# r.net
KiCad netlist of a schematic drawn in EAGLE
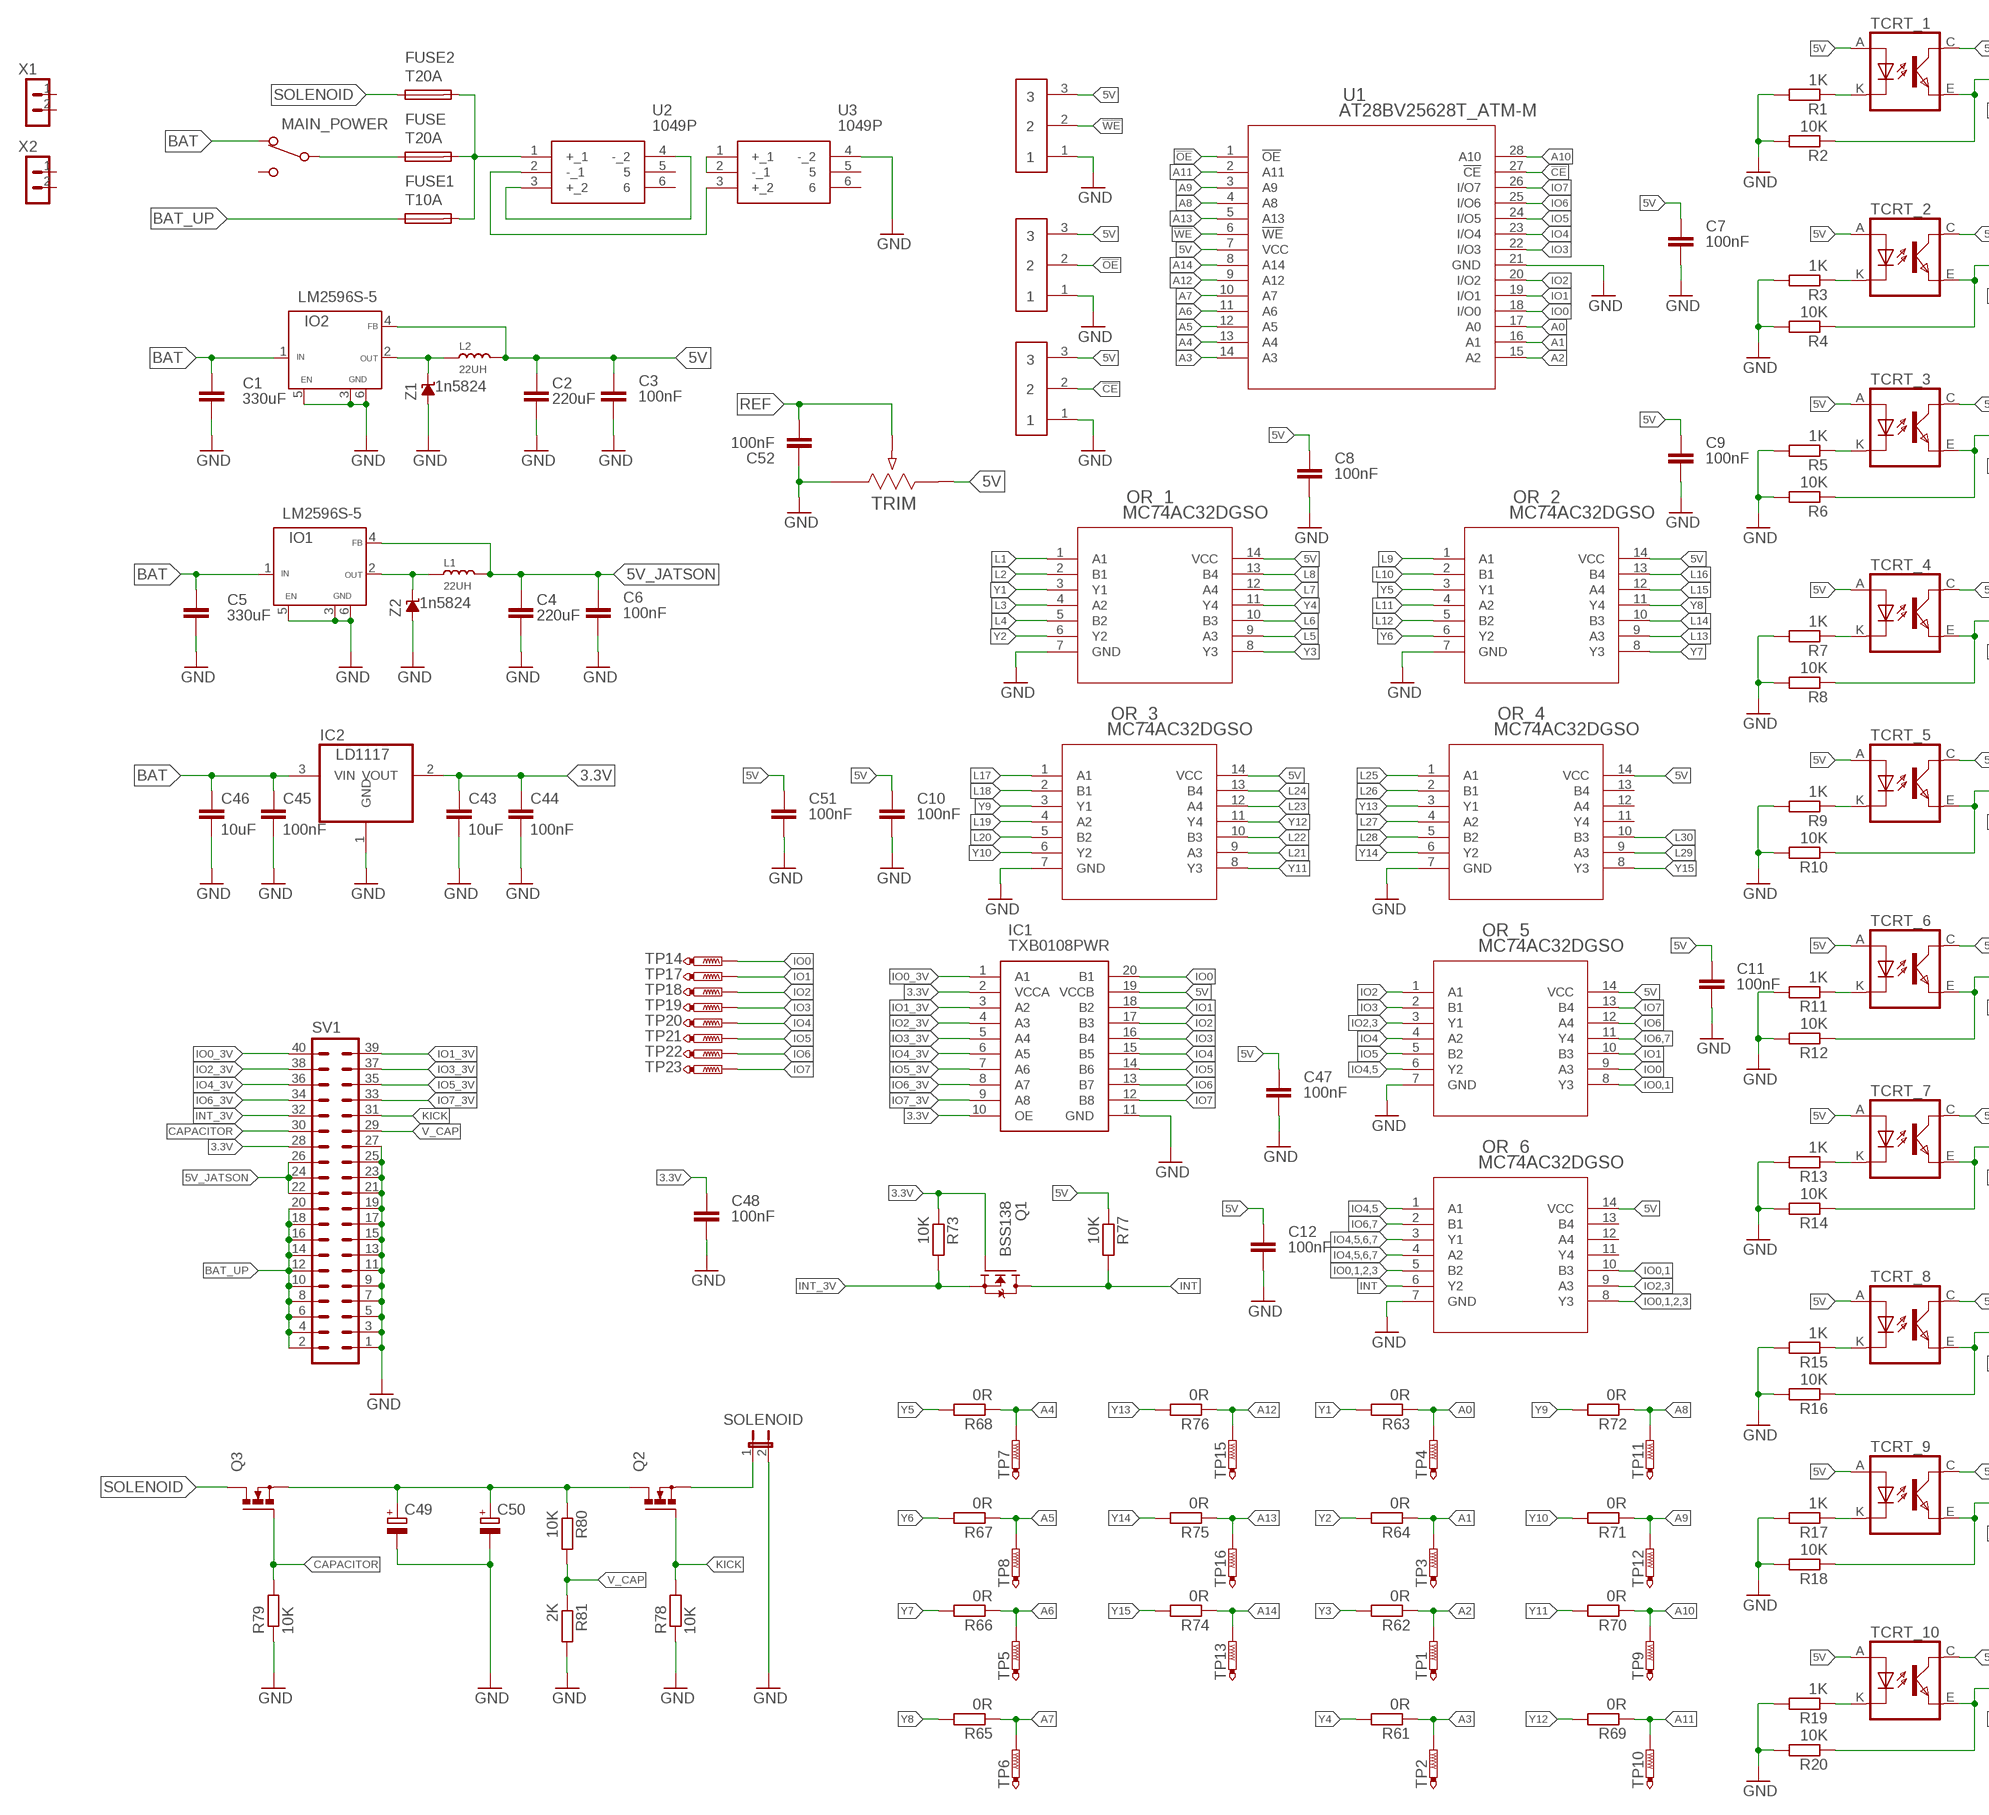
[diagram p0: schematic, sheet 1, part 1 of 2]
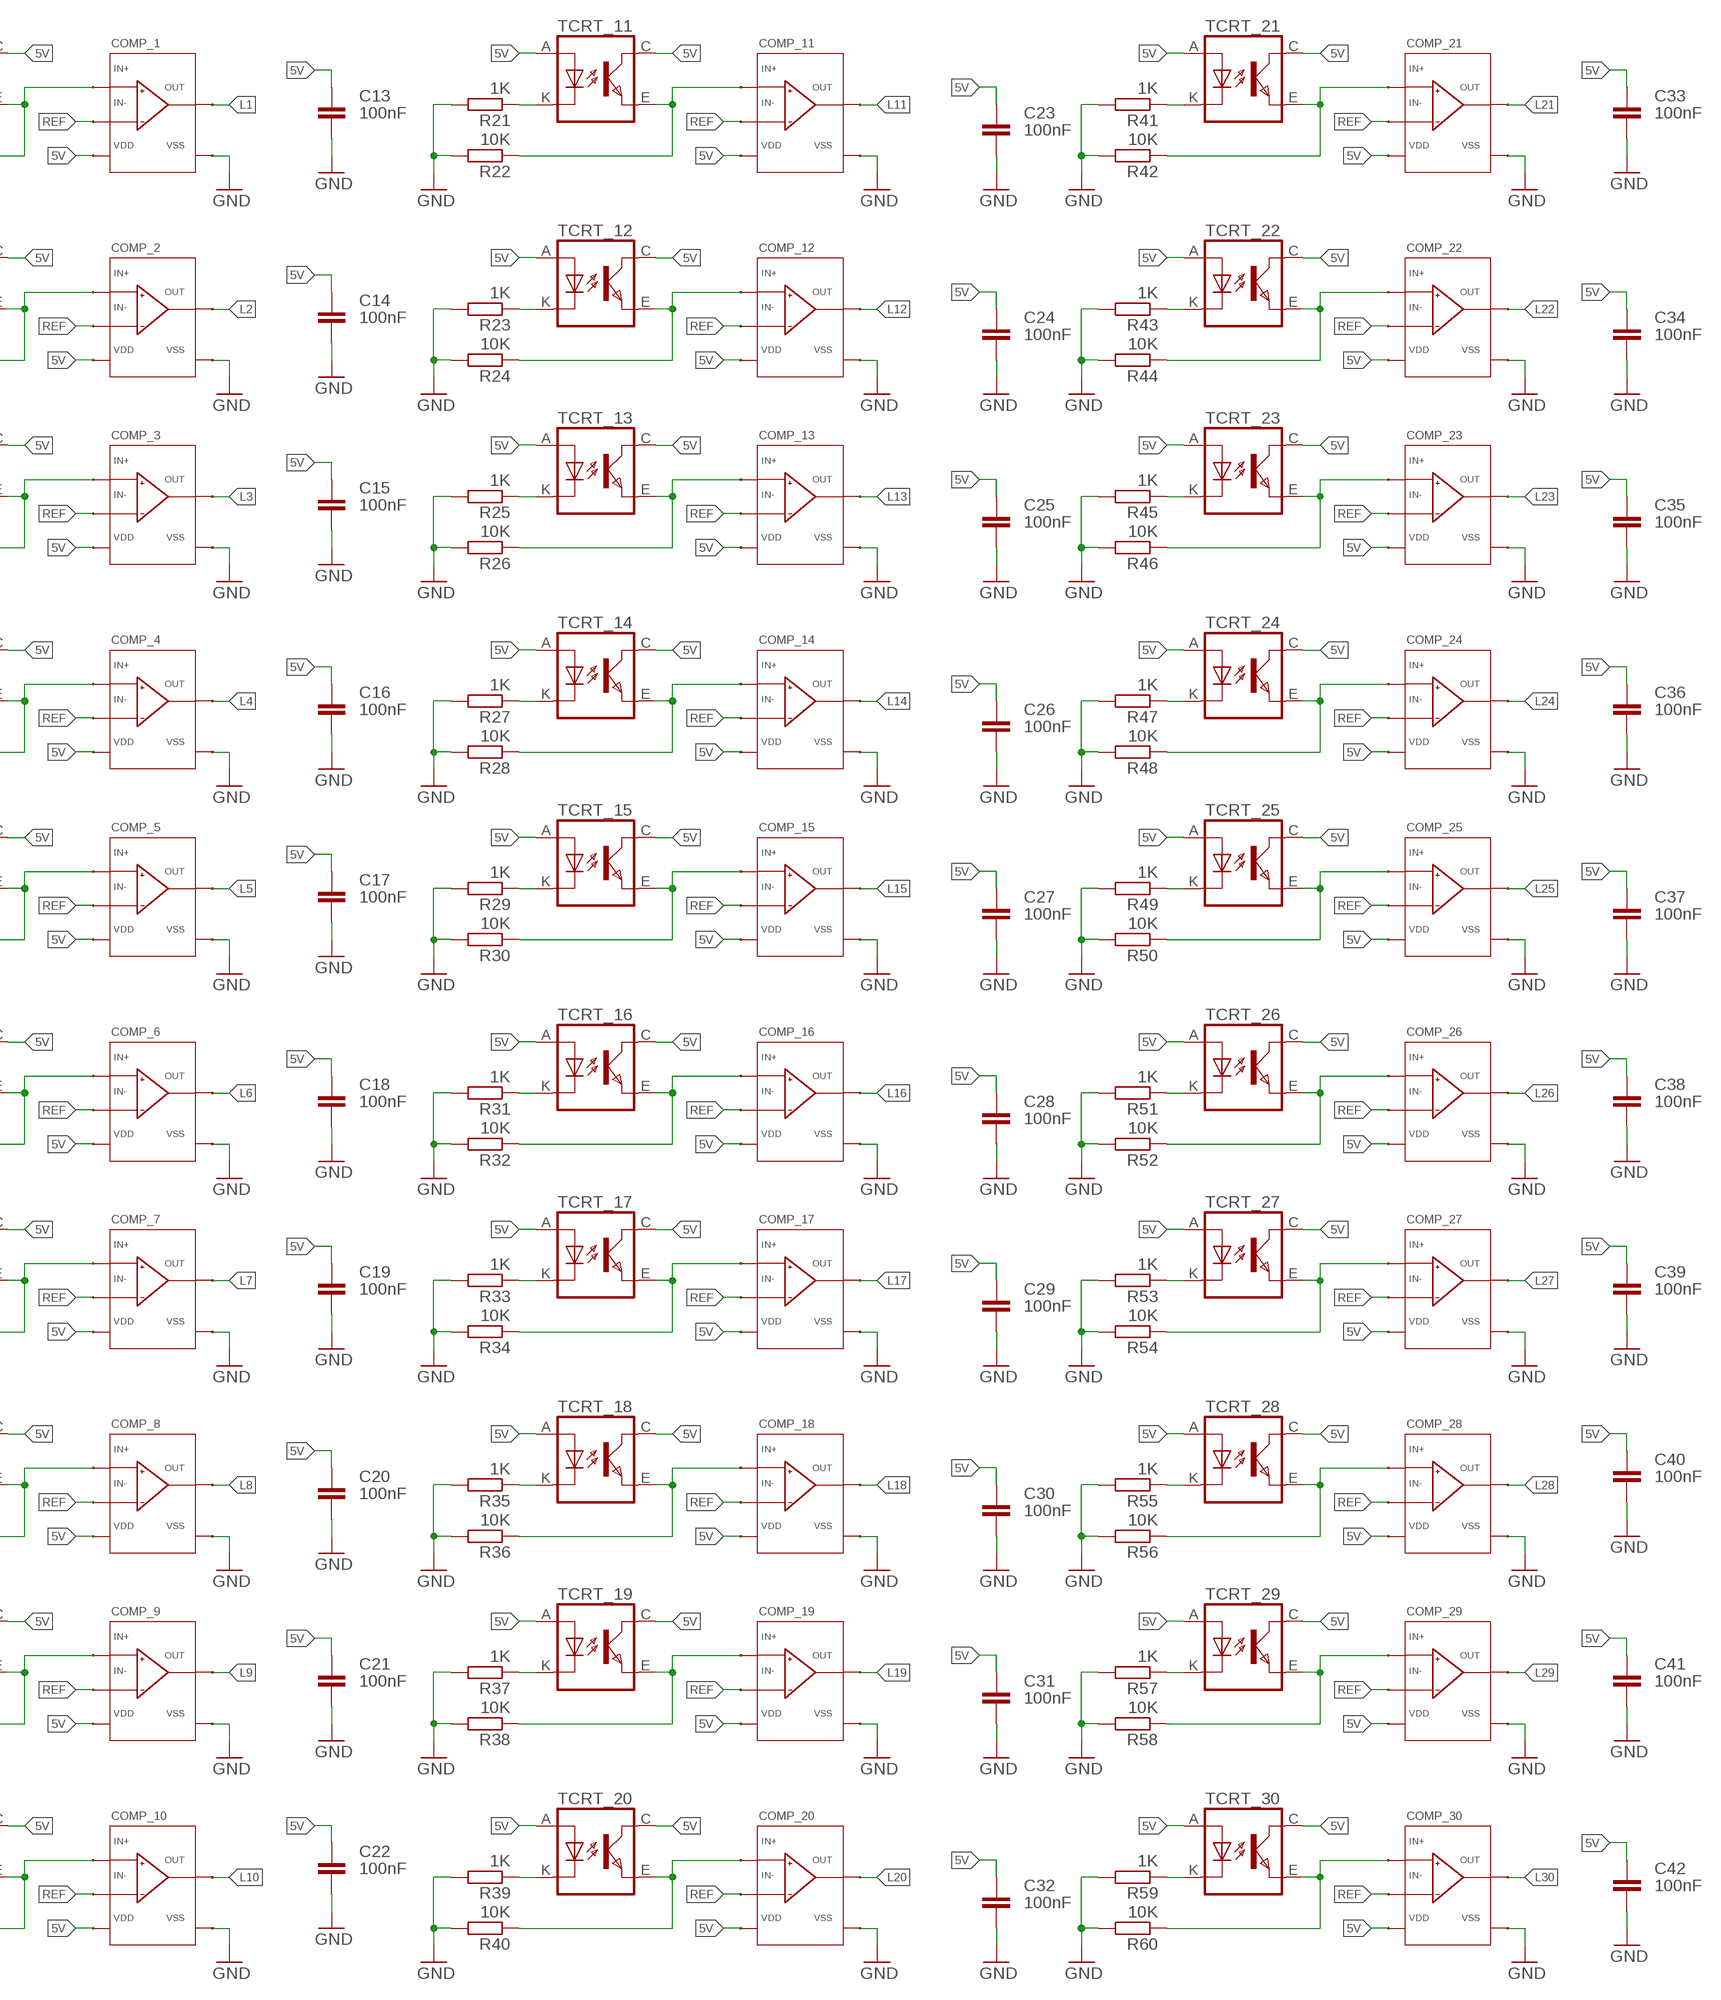
[diagram p1: schematic, sheet 1, part 2 of 2]

(export (version "E")
  (design (tool "Eeschema 10.0.6"))
  (components
    (comp (ref "C1")
      (value "330uF")
      (footprint "eagle-import:CAPM7343X310")
      (libsource (lib "eagle-import") (part "CTANTALUM-2917(7343-METRIC)_"))
    )
    (comp (ref "C2")
      (value "220uF")
      (footprint "eagle-import:CAPM7343X310")
      (libsource (lib "eagle-import") (part "CTANTALUM-2917(7343-METRIC)_"))
    )
    (comp (ref "C3")
      (value "100nF")
      (footprint "eagle-import:C0603")
      (libsource (lib "eagle-import") (part "C-EUC0603"))
    )
    (comp (ref "C4")
      (value "220uF")
      (footprint "eagle-import:CAPM7343X310")
      (libsource (lib "eagle-import") (part "CTANTALUM-2917(7343-METRIC)_"))
    )
    (comp (ref "C5")
      (value "330uF")
      (footprint "eagle-import:CAPM7343X310")
      (libsource (lib "eagle-import") (part "CTANTALUM-2917(7343-METRIC)_"))
    )
    (comp (ref "C6")
      (value "100nF")
      (footprint "eagle-import:C0603")
      (libsource (lib "eagle-import") (part "C-EUC0603"))
    )
    (comp (ref "C7")
      (value "100nF")
      (footprint "eagle-import:C0603")
      (libsource (lib "eagle-import") (part "C-EUC0603"))
    )
    (comp (ref "C8")
      (value "100nF")
      (footprint "eagle-import:C0603")
      (libsource (lib "eagle-import") (part "C-EUC0603"))
    )
    (comp (ref "C9")
      (value "100nF")
      (footprint "eagle-import:C0603")
      (libsource (lib "eagle-import") (part "C-EUC0603"))
    )
    (comp (ref "C10")
      (value "100nF")
      (footprint "eagle-import:C0603")
      (libsource (lib "eagle-import") (part "C-EUC0603"))
    )
    (comp (ref "C11")
      (value "100nF")
      (footprint "eagle-import:C0603")
      (libsource (lib "eagle-import") (part "C-EUC0603"))
    )
    (comp (ref "C12")
      (value "100nF")
      (footprint "eagle-import:C0603")
      (libsource (lib "eagle-import") (part "C-EUC0603"))
    )
    (comp (ref "C13")
      (value "100nF")
      (footprint "eagle-import:C0603")
      (libsource (lib "eagle-import") (part "C-EUC0603"))
    )
    (comp (ref "C14")
      (value "100nF")
      (footprint "eagle-import:C0603")
      (libsource (lib "eagle-import") (part "C-EUC0603"))
    )
    (comp (ref "C15")
      (value "100nF")
      (footprint "eagle-import:C0603")
      (libsource (lib "eagle-import") (part "C-EUC0603"))
    )
    (comp (ref "C16")
      (value "100nF")
      (footprint "eagle-import:C0603")
      (libsource (lib "eagle-import") (part "C-EUC0603"))
    )
    (comp (ref "C17")
      (value "100nF")
      (footprint "eagle-import:C0603")
      (libsource (lib "eagle-import") (part "C-EUC0603"))
    )
    (comp (ref "C18")
      (value "100nF")
      (footprint "eagle-import:C0603")
      (libsource (lib "eagle-import") (part "C-EUC0603"))
    )
    (comp (ref "C19")
      (value "100nF")
      (footprint "eagle-import:C0603")
      (libsource (lib "eagle-import") (part "C-EUC0603"))
    )
    (comp (ref "C20")
      (value "100nF")
      (footprint "eagle-import:C0603")
      (libsource (lib "eagle-import") (part "C-EUC0603"))
    )
    (comp (ref "C21")
      (value "100nF")
      (footprint "eagle-import:C0603")
      (libsource (lib "eagle-import") (part "C-EUC0603"))
    )
    (comp (ref "C22")
      (value "100nF")
      (footprint "eagle-import:C0603")
      (libsource (lib "eagle-import") (part "C-EUC0603"))
    )
    (comp (ref "C23")
      (value "100nF")
      (footprint "eagle-import:C0603")
      (libsource (lib "eagle-import") (part "C-EUC0603"))
    )
    (comp (ref "C24")
      (value "100nF")
      (footprint "eagle-import:C0603")
      (libsource (lib "eagle-import") (part "C-EUC0603"))
    )
    (comp (ref "C25")
      (value "100nF")
      (footprint "eagle-import:C0603")
      (libsource (lib "eagle-import") (part "C-EUC0603"))
    )
    (comp (ref "C26")
      (value "100nF")
      (footprint "eagle-import:C0603")
      (libsource (lib "eagle-import") (part "C-EUC0603"))
    )
    (comp (ref "C27")
      (value "100nF")
      (footprint "eagle-import:C0603")
      (libsource (lib "eagle-import") (part "C-EUC0603"))
    )
    (comp (ref "C28")
      (value "100nF")
      (footprint "eagle-import:C0603")
      (libsource (lib "eagle-import") (part "C-EUC0603"))
    )
    (comp (ref "C29")
      (value "100nF")
      (footprint "eagle-import:C0603")
      (libsource (lib "eagle-import") (part "C-EUC0603"))
    )
    (comp (ref "C30")
      (value "100nF")
      (footprint "eagle-import:C0603")
      (libsource (lib "eagle-import") (part "C-EUC0603"))
    )
    (comp (ref "C31")
      (value "100nF")
      (footprint "eagle-import:C0603")
      (libsource (lib "eagle-import") (part "C-EUC0603"))
    )
    (comp (ref "C32")
      (value "100nF")
      (footprint "eagle-import:C0603")
      (libsource (lib "eagle-import") (part "C-EUC0603"))
    )
    (comp (ref "C33")
      (value "100nF")
      (footprint "eagle-import:C0603")
      (libsource (lib "eagle-import") (part "C-EUC0603"))
    )
    (comp (ref "C34")
      (value "100nF")
      (footprint "eagle-import:C0603")
      (libsource (lib "eagle-import") (part "C-EUC0603"))
    )
    (comp (ref "C35")
      (value "100nF")
      (footprint "eagle-import:C0603")
      (libsource (lib "eagle-import") (part "C-EUC0603"))
    )
    (comp (ref "C36")
      (value "100nF")
      (footprint "eagle-import:C0603")
      (libsource (lib "eagle-import") (part "C-EUC0603"))
    )
    (comp (ref "C37")
      (value "100nF")
      (footprint "eagle-import:C0603")
      (libsource (lib "eagle-import") (part "C-EUC0603"))
    )
    (comp (ref "C38")
      (value "100nF")
      (footprint "eagle-import:C0603")
      (libsource (lib "eagle-import") (part "C-EUC0603"))
    )
    (comp (ref "C39")
      (value "100nF")
      (footprint "eagle-import:C0603")
      (libsource (lib "eagle-import") (part "C-EUC0603"))
    )
    (comp (ref "C40")
      (value "100nF")
      (footprint "eagle-import:C0603")
      (libsource (lib "eagle-import") (part "C-EUC0603"))
    )
    (comp (ref "C41")
      (value "100nF")
      (footprint "eagle-import:C0603")
      (libsource (lib "eagle-import") (part "C-EUC0603"))
    )
    (comp (ref "C42")
      (value "100nF")
      (footprint "eagle-import:C0603")
      (libsource (lib "eagle-import") (part "C-EUC0603"))
    )
    (comp (ref "C43")
      (value "10uF")
      (footprint "eagle-import:C0603")
      (libsource (lib "eagle-import") (part "C-EUC0603"))
    )
    (comp (ref "C44")
      (value "100nF")
      (footprint "eagle-import:C0603")
      (libsource (lib "eagle-import") (part "C-EUC0603"))
    )
    (comp (ref "C45")
      (value "100nF")
      (footprint "eagle-import:C0603")
      (libsource (lib "eagle-import") (part "C-EUC0603"))
    )
    (comp (ref "C46")
      (value "10uF")
      (footprint "eagle-import:C0603")
      (libsource (lib "eagle-import") (part "C-EUC0603"))
    )
    (comp (ref "C47")
      (value "100nF")
      (footprint "eagle-import:C0603")
      (libsource (lib "eagle-import") (part "C-EUC0603"))
    )
    (comp (ref "C48")
      (value "100nF")
      (footprint "eagle-import:C0603")
      (libsource (lib "eagle-import") (part "C-EUC0603"))
    )
    (comp (ref "C49")
      (value "CPOL-EUE10-30")
      (footprint "eagle-import:EB30D")
      (libsource (lib "eagle-import") (part "CPOL-EUE10-30"))
    )
    (comp (ref "C50")
      (value "CPOL-EUE10-30")
      (footprint "eagle-import:EB30D")
      (libsource (lib "eagle-import") (part "CPOL-EUE10-30"))
    )
    (comp (ref "C51")
      (value "100nF")
      (footprint "eagle-import:C0603")
      (libsource (lib "eagle-import") (part "C-EUC0603"))
    )
    (comp (ref "C52")
      (value "100nF")
      (footprint "eagle-import:C0603")
      (libsource (lib "eagle-import") (part "C-EUC0603"))
    )
    (comp (ref "COMP_1")
      (value "TC75S56FUTE85LF")
      (footprint "eagle-import:SOT-353___(USV)_TOS")
      (libsource (lib "eagle-import") (part "TC75S56FUTE85LF"))
    )
    (comp (ref "COMP_2")
      (value "TC75S56FUTE85LF")
      (footprint "eagle-import:SOT-353___(USV)_TOS")
      (libsource (lib "eagle-import") (part "TC75S56FUTE85LF"))
    )
    (comp (ref "COMP_3")
      (value "TC75S56FUTE85LF")
      (footprint "eagle-import:SOT-353___(USV)_TOS")
      (libsource (lib "eagle-import") (part "TC75S56FUTE85LF"))
    )
    (comp (ref "COMP_4")
      (value "TC75S56FUTE85LF")
      (footprint "eagle-import:SOT-353___(USV)_TOS")
      (libsource (lib "eagle-import") (part "TC75S56FUTE85LF"))
    )
    (comp (ref "COMP_5")
      (value "TC75S56FUTE85LF")
      (footprint "eagle-import:SOT-353___(USV)_TOS")
      (libsource (lib "eagle-import") (part "TC75S56FUTE85LF"))
    )
    (comp (ref "COMP_6")
      (value "TC75S56FUTE85LF")
      (footprint "eagle-import:SOT-353___(USV)_TOS")
      (libsource (lib "eagle-import") (part "TC75S56FUTE85LF"))
    )
    (comp (ref "COMP_7")
      (value "TC75S56FUTE85LF")
      (footprint "eagle-import:SOT-353___(USV)_TOS")
      (libsource (lib "eagle-import") (part "TC75S56FUTE85LF"))
    )
    (comp (ref "COMP_8")
      (value "TC75S56FUTE85LF")
      (footprint "eagle-import:SOT-353___(USV)_TOS")
      (libsource (lib "eagle-import") (part "TC75S56FUTE85LF"))
    )
    (comp (ref "COMP_9")
      (value "TC75S56FUTE85LF")
      (footprint "eagle-import:SOT-353___(USV)_TOS")
      (libsource (lib "eagle-import") (part "TC75S56FUTE85LF"))
    )
    (comp (ref "COMP_10")
      (value "TC75S56FUTE85LF")
      (footprint "eagle-import:SOT-353___(USV)_TOS")
      (libsource (lib "eagle-import") (part "TC75S56FUTE85LF"))
    )
    (comp (ref "COMP_11")
      (value "TC75S56FUTE85LF")
      (footprint "eagle-import:SOT-353___(USV)_TOS")
      (libsource (lib "eagle-import") (part "TC75S56FUTE85LF"))
    )
    (comp (ref "COMP_12")
      (value "TC75S56FUTE85LF")
      (footprint "eagle-import:SOT-353___(USV)_TOS")
      (libsource (lib "eagle-import") (part "TC75S56FUTE85LF"))
    )
    (comp (ref "COMP_13")
      (value "TC75S56FUTE85LF")
      (footprint "eagle-import:SOT-353___(USV)_TOS")
      (libsource (lib "eagle-import") (part "TC75S56FUTE85LF"))
    )
    (comp (ref "COMP_14")
      (value "TC75S56FUTE85LF")
      (footprint "eagle-import:SOT-353___(USV)_TOS")
      (libsource (lib "eagle-import") (part "TC75S56FUTE85LF"))
    )
    (comp (ref "COMP_15")
      (value "TC75S56FUTE85LF")
      (footprint "eagle-import:SOT-353___(USV)_TOS")
      (libsource (lib "eagle-import") (part "TC75S56FUTE85LF"))
    )
    (comp (ref "COMP_16")
      (value "TC75S56FUTE85LF")
      (footprint "eagle-import:SOT-353___(USV)_TOS")
      (libsource (lib "eagle-import") (part "TC75S56FUTE85LF"))
    )
    (comp (ref "COMP_17")
      (value "TC75S56FUTE85LF")
      (footprint "eagle-import:SOT-353___(USV)_TOS")
      (libsource (lib "eagle-import") (part "TC75S56FUTE85LF"))
    )
    (comp (ref "COMP_18")
      (value "TC75S56FUTE85LF")
      (footprint "eagle-import:SOT-353___(USV)_TOS")
      (libsource (lib "eagle-import") (part "TC75S56FUTE85LF"))
    )
    (comp (ref "COMP_19")
      (value "TC75S56FUTE85LF")
      (footprint "eagle-import:SOT-353___(USV)_TOS")
      (libsource (lib "eagle-import") (part "TC75S56FUTE85LF"))
    )
    (comp (ref "COMP_20")
      (value "TC75S56FUTE85LF")
      (footprint "eagle-import:SOT-353___(USV)_TOS")
      (libsource (lib "eagle-import") (part "TC75S56FUTE85LF"))
    )
    (comp (ref "COMP_21")
      (value "TC75S56FUTE85LF")
      (footprint "eagle-import:SOT-353___(USV)_TOS")
      (libsource (lib "eagle-import") (part "TC75S56FUTE85LF"))
    )
    (comp (ref "COMP_22")
      (value "TC75S56FUTE85LF")
      (footprint "eagle-import:SOT-353___(USV)_TOS")
      (libsource (lib "eagle-import") (part "TC75S56FUTE85LF"))
    )
    (comp (ref "COMP_23")
      (value "TC75S56FUTE85LF")
      (footprint "eagle-import:SOT-353___(USV)_TOS")
      (libsource (lib "eagle-import") (part "TC75S56FUTE85LF"))
    )
    (comp (ref "COMP_24")
      (value "TC75S56FUTE85LF")
      (footprint "eagle-import:SOT-353___(USV)_TOS")
      (libsource (lib "eagle-import") (part "TC75S56FUTE85LF"))
    )
    (comp (ref "COMP_25")
      (value "TC75S56FUTE85LF")
      (footprint "eagle-import:SOT-353___(USV)_TOS")
      (libsource (lib "eagle-import") (part "TC75S56FUTE85LF"))
    )
    (comp (ref "COMP_26")
      (value "TC75S56FUTE85LF")
      (footprint "eagle-import:SOT-353___(USV)_TOS")
      (libsource (lib "eagle-import") (part "TC75S56FUTE85LF"))
    )
    (comp (ref "COMP_27")
      (value "TC75S56FUTE85LF")
      (footprint "eagle-import:SOT-353___(USV)_TOS")
      (libsource (lib "eagle-import") (part "TC75S56FUTE85LF"))
    )
    (comp (ref "COMP_28")
      (value "TC75S56FUTE85LF")
      (footprint "eagle-import:SOT-353___(USV)_TOS")
      (libsource (lib "eagle-import") (part "TC75S56FUTE85LF"))
    )
    (comp (ref "COMP_29")
      (value "TC75S56FUTE85LF")
      (footprint "eagle-import:SOT-353___(USV)_TOS")
      (libsource (lib "eagle-import") (part "TC75S56FUTE85LF"))
    )
    (comp (ref "COMP_30")
      (value "TC75S56FUTE85LF")
      (footprint "eagle-import:SOT-353___(USV)_TOS")
      (libsource (lib "eagle-import") (part "TC75S56FUTE85LF"))
    )
    (comp (ref "FUSE")
      (value "T20A")
      (footprint "eagle-import:SH22,5A")
      (libsource (lib "eagle-import") (part "POISTKA2A"))
    )
    (comp (ref "FUSE1")
      (value "T10A")
      (footprint "eagle-import:SH22,5A")
      (libsource (lib "eagle-import") (part "POISTKA2A"))
    )
    (comp (ref "FUSE2")
      (value "T20A")
      (footprint "eagle-import:SH22,5A")
      (libsource (lib "eagle-import") (part "POISTKA2A"))
    )
    (comp (ref "IC1")
      (value "TXB0108PWR")
      (footprint "eagle-import:SOP65P640X120-20N")
      (fields (field (name "MOUSER_PART_NUMBER") "595-TXB0108PWR"))
      (libsource (lib "eagle-import") (part "TXB0108PWR"))
    )
    (comp (ref "IC2")
      (value "LD1117")
      (footprint "eagle-import:SOT223")
      (fields (field (name "MF") "TEXAS INSTRUMENTS") (field (name "MPN") "REG1117FAKTTT"))
      (libsource (lib "eagle-import") (part "LD1117"))
    )
    (comp (ref "IO1")
      (value "LM2596S-5")
      (footprint "eagle-import:TO263-5")
      (libsource (lib "eagle-import") (part "LM2596S"))
    )
    (comp (ref "IO2")
      (value "LM2596S-5")
      (footprint "eagle-import:TO263-5")
      (libsource (lib "eagle-import") (part "LM2596S"))
    )
    (comp (ref "L1")
      (value "22UH")
      (footprint "eagle-import:INDUCTOR_L0630")
      (libsource (lib "eagle-import") (part "INDUCTOR/FERRITE-BEAD0630"))
    )
    (comp (ref "L2")
      (value "22UH")
      (footprint "eagle-import:INDUCTOR_L0630")
      (libsource (lib "eagle-import") (part "INDUCTOR/FERRITE-BEAD0630"))
    )
    (comp (ref "MAIN_POWER")
      (value "PREP-1PB")
      (footprint "eagle-import:P-B069B")
      (libsource (lib "eagle-import") (part "PREP-1PB"))
    )
    (comp (ref "OR_1")
      (value "MC74AC32DGSO")
      (footprint "eagle-import:SOIC-14_NB_ONS-M")
      (fields
        (field (name "MANUFACTURER_PART_NUMBER") "MC74VHC32DR2G")
        (field (name "COPYRIGHT") "Copyright (C) 2016 Accelerated Designs. All rights reserved")
      )
      (libsource (lib "eagle-import") (part "MC74AC32DGSOIC-14_NB_ONS-M"))
    )
    (comp (ref "OR_2")
      (value "MC74AC32DGSO")
      (footprint "eagle-import:SOIC-14_NB_ONS-M")
      (fields
        (field (name "MANUFACTURER_PART_NUMBER") "MC74VHC32DR2G")
        (field (name "COPYRIGHT") "Copyright (C) 2016 Accelerated Designs. All rights reserved")
      )
      (libsource (lib "eagle-import") (part "MC74AC32DGSOIC-14_NB_ONS-M"))
    )
    (comp (ref "OR_3")
      (value "MC74AC32DGSO")
      (footprint "eagle-import:SOIC-14_NB_ONS-M")
      (fields
        (field (name "MANUFACTURER_PART_NUMBER") "MC74VHC32DR2G")
        (field (name "COPYRIGHT") "Copyright (C) 2016 Accelerated Designs. All rights reserved")
      )
      (libsource (lib "eagle-import") (part "MC74AC32DGSOIC-14_NB_ONS-M"))
    )
    (comp (ref "OR_4")
      (value "MC74AC32DGSO")
      (footprint "eagle-import:SOIC-14_NB_ONS-M")
      (fields
        (field (name "MANUFACTURER_PART_NUMBER") "MC74VHC32DR2G")
        (field (name "COPYRIGHT") "Copyright (C) 2016 Accelerated Designs. All rights reserved")
      )
      (libsource (lib "eagle-import") (part "MC74AC32DGSOIC-14_NB_ONS-M"))
    )
    (comp (ref "OR_5")
      (value "MC74AC32DGSO")
      (footprint "eagle-import:SOIC-14_NB_ONS-M")
      (fields
        (field (name "MANUFACTURER_PART_NUMBER") "MC74VHC32DR2G")
        (field (name "COPYRIGHT") "Copyright (C) 2016 Accelerated Designs. All rights reserved")
      )
      (libsource (lib "eagle-import") (part "MC74AC32DGSOIC-14_NB_ONS-M"))
    )
    (comp (ref "OR_6")
      (value "MC74AC32DGSO")
      (footprint "eagle-import:SOIC-14_NB_ONS-M")
      (fields
        (field (name "MANUFACTURER_PART_NUMBER") "MC74VHC32DR2G")
        (field (name "COPYRIGHT") "Copyright (C) 2016 Accelerated Designs. All rights reserved")
      )
      (libsource (lib "eagle-import") (part "MC74AC32DGSOIC-14_NB_ONS-M"))
    )
    (comp (ref "Q1")
      (value "BSS138")
      (footprint "eagle-import:SOT23")
      (fields (field (name "MF") "Fairchild"))
      (libsource (lib "eagle-import") (part "BSS138"))
    )
    (comp (ref "Q2")
      (value "PMOSFET_NTO220BV")
      (footprint "eagle-import:TO220BV")
      (libsource (lib "eagle-import") (part "PMOSFET_NTO220BV"))
    )
    (comp (ref "Q3")
      (value "PMOSFET_NTO220BV")
      (footprint "eagle-import:TO220BV")
      (libsource (lib "eagle-import") (part "PMOSFET_NTO220BV"))
    )
    (comp (ref "R1")
      (value "1K")
      (footprint "eagle-import:R0603")
      (libsource (lib "eagle-import") (part "R-EU_R0603"))
    )
    (comp (ref "R2")
      (value "10K")
      (footprint "eagle-import:R0603")
      (libsource (lib "eagle-import") (part "R-EU_R0603"))
    )
    (comp (ref "R3")
      (value "1K")
      (footprint "eagle-import:R0603")
      (libsource (lib "eagle-import") (part "R-EU_R0603"))
    )
    (comp (ref "R4")
      (value "10K")
      (footprint "eagle-import:R0603")
      (libsource (lib "eagle-import") (part "R-EU_R0603"))
    )
    (comp (ref "R5")
      (value "1K")
      (footprint "eagle-import:R0603")
      (libsource (lib "eagle-import") (part "R-EU_R0603"))
    )
    (comp (ref "R6")
      (value "10K")
      (footprint "eagle-import:R0603")
      (libsource (lib "eagle-import") (part "R-EU_R0603"))
    )
    (comp (ref "R7")
      (value "1K")
      (footprint "eagle-import:R0603")
      (libsource (lib "eagle-import") (part "R-EU_R0603"))
    )
    (comp (ref "R8")
      (value "10K")
      (footprint "eagle-import:R0603")
      (libsource (lib "eagle-import") (part "R-EU_R0603"))
    )
    (comp (ref "R9")
      (value "1K")
      (footprint "eagle-import:R0603")
      (libsource (lib "eagle-import") (part "R-EU_R0603"))
    )
    (comp (ref "R10")
      (value "10K")
      (footprint "eagle-import:R0603")
      (libsource (lib "eagle-import") (part "R-EU_R0603"))
    )
    (comp (ref "R11")
      (value "1K")
      (footprint "eagle-import:R0603")
      (libsource (lib "eagle-import") (part "R-EU_R0603"))
    )
    (comp (ref "R12")
      (value "10K")
      (footprint "eagle-import:R0603")
      (libsource (lib "eagle-import") (part "R-EU_R0603"))
    )
    (comp (ref "R13")
      (value "1K")
      (footprint "eagle-import:R0603")
      (libsource (lib "eagle-import") (part "R-EU_R0603"))
    )
    (comp (ref "R14")
      (value "10K")
      (footprint "eagle-import:R0603")
      (libsource (lib "eagle-import") (part "R-EU_R0603"))
    )
    (comp (ref "R15")
      (value "1K")
      (footprint "eagle-import:R0603")
      (libsource (lib "eagle-import") (part "R-EU_R0603"))
    )
    (comp (ref "R16")
      (value "10K")
      (footprint "eagle-import:R0603")
      (libsource (lib "eagle-import") (part "R-EU_R0603"))
    )
    (comp (ref "R17")
      (value "1K")
      (footprint "eagle-import:R0603")
      (libsource (lib "eagle-import") (part "R-EU_R0603"))
    )
    (comp (ref "R18")
      (value "10K")
      (footprint "eagle-import:R0603")
      (libsource (lib "eagle-import") (part "R-EU_R0603"))
    )
    (comp (ref "R19")
      (value "1K")
      (footprint "eagle-import:R0603")
      (libsource (lib "eagle-import") (part "R-EU_R0603"))
    )
    (comp (ref "R20")
      (value "10K")
      (footprint "eagle-import:R0603")
      (libsource (lib "eagle-import") (part "R-EU_R0603"))
    )
    (comp (ref "R21")
      (value "1K")
      (footprint "eagle-import:R0603")
      (libsource (lib "eagle-import") (part "R-EU_R0603"))
    )
    (comp (ref "R22")
      (value "10K")
      (footprint "eagle-import:R0603")
      (libsource (lib "eagle-import") (part "R-EU_R0603"))
    )
    (comp (ref "R23")
      (value "1K")
      (footprint "eagle-import:R0603")
      (libsource (lib "eagle-import") (part "R-EU_R0603"))
    )
    (comp (ref "R24")
      (value "10K")
      (footprint "eagle-import:R0603")
      (libsource (lib "eagle-import") (part "R-EU_R0603"))
    )
    (comp (ref "R25")
      (value "1K")
      (footprint "eagle-import:R0603")
      (libsource (lib "eagle-import") (part "R-EU_R0603"))
    )
    (comp (ref "R26")
      (value "10K")
      (footprint "eagle-import:R0603")
      (libsource (lib "eagle-import") (part "R-EU_R0603"))
    )
    (comp (ref "R27")
      (value "1K")
      (footprint "eagle-import:R0603")
      (libsource (lib "eagle-import") (part "R-EU_R0603"))
    )
    (comp (ref "R28")
      (value "10K")
      (footprint "eagle-import:R0603")
      (libsource (lib "eagle-import") (part "R-EU_R0603"))
    )
    (comp (ref "R29")
      (value "1K")
      (footprint "eagle-import:R0603")
      (libsource (lib "eagle-import") (part "R-EU_R0603"))
    )
    (comp (ref "R30")
      (value "10K")
      (footprint "eagle-import:R0603")
      (libsource (lib "eagle-import") (part "R-EU_R0603"))
    )
    (comp (ref "R31")
      (value "1K")
      (footprint "eagle-import:R0603")
      (libsource (lib "eagle-import") (part "R-EU_R0603"))
    )
    (comp (ref "R32")
      (value "10K")
      (footprint "eagle-import:R0603")
      (libsource (lib "eagle-import") (part "R-EU_R0603"))
    )
    (comp (ref "R33")
      (value "1K")
      (footprint "eagle-import:R0603")
      (libsource (lib "eagle-import") (part "R-EU_R0603"))
    )
    (comp (ref "R34")
      (value "10K")
      (footprint "eagle-import:R0603")
      (libsource (lib "eagle-import") (part "R-EU_R0603"))
    )
    (comp (ref "R35")
      (value "1K")
      (footprint "eagle-import:R0603")
      (libsource (lib "eagle-import") (part "R-EU_R0603"))
    )
    (comp (ref "R36")
      (value "10K")
      (footprint "eagle-import:R0603")
      (libsource (lib "eagle-import") (part "R-EU_R0603"))
    )
    (comp (ref "R37")
      (value "1K")
      (footprint "eagle-import:R0603")
      (libsource (lib "eagle-import") (part "R-EU_R0603"))
    )
    (comp (ref "R38")
      (value "10K")
      (footprint "eagle-import:R0603")
      (libsource (lib "eagle-import") (part "R-EU_R0603"))
    )
    (comp (ref "R39")
      (value "1K")
      (footprint "eagle-import:R0603")
      (libsource (lib "eagle-import") (part "R-EU_R0603"))
    )
    (comp (ref "R40")
      (value "10K")
      (footprint "eagle-import:R0603")
      (libsource (lib "eagle-import") (part "R-EU_R0603"))
    )
    (comp (ref "R41")
      (value "1K")
      (footprint "eagle-import:R0603")
      (libsource (lib "eagle-import") (part "R-EU_R0603"))
    )
    (comp (ref "R42")
      (value "10K")
      (footprint "eagle-import:R0603")
      (libsource (lib "eagle-import") (part "R-EU_R0603"))
    )
    (comp (ref "R43")
      (value "1K")
      (footprint "eagle-import:R0603")
      (libsource (lib "eagle-import") (part "R-EU_R0603"))
    )
    (comp (ref "R44")
      (value "10K")
      (footprint "eagle-import:R0603")
      (libsource (lib "eagle-import") (part "R-EU_R0603"))
    )
    (comp (ref "R45")
      (value "1K")
      (footprint "eagle-import:R0603")
      (libsource (lib "eagle-import") (part "R-EU_R0603"))
    )
    (comp (ref "R46")
      (value "10K")
      (footprint "eagle-import:R0603")
      (libsource (lib "eagle-import") (part "R-EU_R0603"))
    )
    (comp (ref "R47")
      (value "1K")
      (footprint "eagle-import:R0603")
      (libsource (lib "eagle-import") (part "R-EU_R0603"))
    )
    (comp (ref "R48")
      (value "10K")
      (footprint "eagle-import:R0603")
      (libsource (lib "eagle-import") (part "R-EU_R0603"))
    )
    (comp (ref "R49")
      (value "1K")
      (footprint "eagle-import:R0603")
      (libsource (lib "eagle-import") (part "R-EU_R0603"))
    )
    (comp (ref "R50")
      (value "10K")
      (footprint "eagle-import:R0603")
      (libsource (lib "eagle-import") (part "R-EU_R0603"))
    )
    (comp (ref "R51")
      (value "1K")
      (footprint "eagle-import:R0603")
      (libsource (lib "eagle-import") (part "R-EU_R0603"))
    )
    (comp (ref "R52")
      (value "10K")
      (footprint "eagle-import:R0603")
      (libsource (lib "eagle-import") (part "R-EU_R0603"))
    )
    (comp (ref "R53")
      (value "1K")
      (footprint "eagle-import:R0603")
      (libsource (lib "eagle-import") (part "R-EU_R0603"))
    )
    (comp (ref "R54")
      (value "10K")
      (footprint "eagle-import:R0603")
      (libsource (lib "eagle-import") (part "R-EU_R0603"))
    )
    (comp (ref "R55")
      (value "1K")
      (footprint "eagle-import:R0603")
      (libsource (lib "eagle-import") (part "R-EU_R0603"))
    )
    (comp (ref "R56")
      (value "10K")
      (footprint "eagle-import:R0603")
      (libsource (lib "eagle-import") (part "R-EU_R0603"))
    )
    (comp (ref "R57")
      (value "1K")
      (footprint "eagle-import:R0603")
      (libsource (lib "eagle-import") (part "R-EU_R0603"))
    )
    (comp (ref "R58")
      (value "10K")
      (footprint "eagle-import:R0603")
      (libsource (lib "eagle-import") (part "R-EU_R0603"))
    )
    (comp (ref "R59")
      (value "1K")
      (footprint "eagle-import:R0603")
      (libsource (lib "eagle-import") (part "R-EU_R0603"))
    )
    (comp (ref "R60")
      (value "10K")
      (footprint "eagle-import:R0603")
      (libsource (lib "eagle-import") (part "R-EU_R0603"))
    )
    (comp (ref "R61")
      (value "0R")
      (footprint "eagle-import:R0603")
      (libsource (lib "eagle-import") (part "R-EU_R0603"))
    )
    (comp (ref "R62")
      (value "0R")
      (footprint "eagle-import:R0603")
      (libsource (lib "eagle-import") (part "R-EU_R0603"))
    )
    (comp (ref "R63")
      (value "0R")
      (footprint "eagle-import:R0603")
      (libsource (lib "eagle-import") (part "R-EU_R0603"))
    )
    (comp (ref "R64")
      (value "0R")
      (footprint "eagle-import:R0603")
      (libsource (lib "eagle-import") (part "R-EU_R0603"))
    )
    (comp (ref "R65")
      (value "0R")
      (footprint "eagle-import:R0603")
      (libsource (lib "eagle-import") (part "R-EU_R0603"))
    )
    (comp (ref "R66")
      (value "0R")
      (footprint "eagle-import:R0603")
      (libsource (lib "eagle-import") (part "R-EU_R0603"))
    )
    (comp (ref "R67")
      (value "0R")
      (footprint "eagle-import:R0603")
      (libsource (lib "eagle-import") (part "R-EU_R0603"))
    )
    (comp (ref "R68")
      (value "0R")
      (footprint "eagle-import:R0603")
      (libsource (lib "eagle-import") (part "R-EU_R0603"))
    )
    (comp (ref "R69")
      (value "0R")
      (footprint "eagle-import:R0603")
      (libsource (lib "eagle-import") (part "R-EU_R0603"))
    )
    (comp (ref "R70")
      (value "0R")
      (footprint "eagle-import:R0603")
      (libsource (lib "eagle-import") (part "R-EU_R0603"))
    )
    (comp (ref "R71")
      (value "0R")
      (footprint "eagle-import:R0603")
      (libsource (lib "eagle-import") (part "R-EU_R0603"))
    )
    (comp (ref "R72")
      (value "0R")
      (footprint "eagle-import:R0603")
      (libsource (lib "eagle-import") (part "R-EU_R0603"))
    )
    (comp (ref "R73")
      (value "10K")
      (footprint "eagle-import:R0603")
      (libsource (lib "eagle-import") (part "R-EU_R0603"))
    )
    (comp (ref "R74")
      (value "0R")
      (footprint "eagle-import:R0603")
      (libsource (lib "eagle-import") (part "R-EU_R0603"))
    )
    (comp (ref "R75")
      (value "0R")
      (footprint "eagle-import:R0603")
      (libsource (lib "eagle-import") (part "R-EU_R0603"))
    )
    (comp (ref "R76")
      (value "0R")
      (footprint "eagle-import:R0603")
      (libsource (lib "eagle-import") (part "R-EU_R0603"))
    )
    (comp (ref "R77")
      (value "10K")
      (footprint "eagle-import:R0603")
      (libsource (lib "eagle-import") (part "R-EU_R0603"))
    )
    (comp (ref "R78")
      (value "10K")
      (footprint "eagle-import:R1206")
      (libsource (lib "eagle-import") (part "R-EU_R1206"))
    )
    (comp (ref "R79")
      (value "10K")
      (footprint "eagle-import:R1206")
      (libsource (lib "eagle-import") (part "R-EU_R1206"))
    )
    (comp (ref "R80")
      (value "10K")
      (footprint "eagle-import:R0603")
      (libsource (lib "eagle-import") (part "R-EU_R0603"))
    )
    (comp (ref "R81")
      (value "2K")
      (footprint "eagle-import:R0603")
      (libsource (lib "eagle-import") (part "R-EU_R0603"))
    )
    (comp (ref "SOLENOID")
      (value "JP1E")
      (footprint "eagle-import:JP1")
      (libsource (lib "eagle-import") (part "JP1E"))
    )
    (comp (ref "SV1")
      (value "MLW40")
      (footprint "eagle-import:ML40")
      (libsource (lib "eagle-import") (part "MLW40"))
    )
    (comp (ref "TCRT_1")
      (value "TCRT5000")
      (footprint "eagle-import:TCRT5000")
      (libsource (lib "eagle-import") (part "TCRT5000"))
    )
    (comp (ref "TCRT_2")
      (value "TCRT5000")
      (footprint "eagle-import:TCRT5000")
      (libsource (lib "eagle-import") (part "TCRT5000"))
    )
    (comp (ref "TCRT_3")
      (value "TCRT5000")
      (footprint "eagle-import:TCRT5000")
      (libsource (lib "eagle-import") (part "TCRT5000"))
    )
    (comp (ref "TCRT_4")
      (value "TCRT5000")
      (footprint "eagle-import:TCRT5000")
      (libsource (lib "eagle-import") (part "TCRT5000"))
    )
    (comp (ref "TCRT_5")
      (value "TCRT5000")
      (footprint "eagle-import:TCRT5000")
      (libsource (lib "eagle-import") (part "TCRT5000"))
    )
    (comp (ref "TCRT_6")
      (value "TCRT5000")
      (footprint "eagle-import:TCRT5000")
      (libsource (lib "eagle-import") (part "TCRT5000"))
    )
    (comp (ref "TCRT_7")
      (value "TCRT5000")
      (footprint "eagle-import:TCRT5000")
      (libsource (lib "eagle-import") (part "TCRT5000"))
    )
    (comp (ref "TCRT_8")
      (value "TCRT5000")
      (footprint "eagle-import:TCRT5000")
      (libsource (lib "eagle-import") (part "TCRT5000"))
    )
    (comp (ref "TCRT_9")
      (value "TCRT5000")
      (footprint "eagle-import:TCRT5000")
      (libsource (lib "eagle-import") (part "TCRT5000"))
    )
    (comp (ref "TCRT_10")
      (value "TCRT5000")
      (footprint "eagle-import:TCRT5000")
      (libsource (lib "eagle-import") (part "TCRT5000"))
    )
    (comp (ref "TCRT_11")
      (value "TCRT5000")
      (footprint "eagle-import:TCRT5000")
      (libsource (lib "eagle-import") (part "TCRT5000"))
    )
    (comp (ref "TCRT_12")
      (value "TCRT5000")
      (footprint "eagle-import:TCRT5000")
      (libsource (lib "eagle-import") (part "TCRT5000"))
    )
    (comp (ref "TCRT_13")
      (value "TCRT5000")
      (footprint "eagle-import:TCRT5000")
      (libsource (lib "eagle-import") (part "TCRT5000"))
    )
    (comp (ref "TCRT_14")
      (value "TCRT5000")
      (footprint "eagle-import:TCRT5000")
      (libsource (lib "eagle-import") (part "TCRT5000"))
    )
    (comp (ref "TCRT_15")
      (value "TCRT5000")
      (footprint "eagle-import:TCRT5000")
      (libsource (lib "eagle-import") (part "TCRT5000"))
    )
    (comp (ref "TCRT_16")
      (value "TCRT5000")
      (footprint "eagle-import:TCRT5000")
      (libsource (lib "eagle-import") (part "TCRT5000"))
    )
    (comp (ref "TCRT_17")
      (value "TCRT5000")
      (footprint "eagle-import:TCRT5000")
      (libsource (lib "eagle-import") (part "TCRT5000"))
    )
    (comp (ref "TCRT_18")
      (value "TCRT5000")
      (footprint "eagle-import:TCRT5000")
      (libsource (lib "eagle-import") (part "TCRT5000"))
    )
    (comp (ref "TCRT_19")
      (value "TCRT5000")
      (footprint "eagle-import:TCRT5000")
      (libsource (lib "eagle-import") (part "TCRT5000"))
    )
    (comp (ref "TCRT_20")
      (value "TCRT5000")
      (footprint "eagle-import:TCRT5000")
      (libsource (lib "eagle-import") (part "TCRT5000"))
    )
    (comp (ref "TCRT_21")
      (value "TCRT5000")
      (footprint "eagle-import:TCRT5000")
      (libsource (lib "eagle-import") (part "TCRT5000"))
    )
    (comp (ref "TCRT_22")
      (value "TCRT5000")
      (footprint "eagle-import:TCRT5000")
      (libsource (lib "eagle-import") (part "TCRT5000"))
    )
    (comp (ref "TCRT_23")
      (value "TCRT5000")
      (footprint "eagle-import:TCRT5000")
      (libsource (lib "eagle-import") (part "TCRT5000"))
    )
    (comp (ref "TCRT_24")
      (value "TCRT5000")
      (footprint "eagle-import:TCRT5000")
      (libsource (lib "eagle-import") (part "TCRT5000"))
    )
    (comp (ref "TCRT_25")
      (value "TCRT5000")
      (footprint "eagle-import:TCRT5000")
      (libsource (lib "eagle-import") (part "TCRT5000"))
    )
    (comp (ref "TCRT_26")
      (value "TCRT5000")
      (footprint "eagle-import:TCRT5000")
      (libsource (lib "eagle-import") (part "TCRT5000"))
    )
    (comp (ref "TCRT_27")
      (value "TCRT5000")
      (footprint "eagle-import:TCRT5000")
      (libsource (lib "eagle-import") (part "TCRT5000"))
    )
    (comp (ref "TCRT_28")
      (value "TCRT5000")
      (footprint "eagle-import:TCRT5000")
      (libsource (lib "eagle-import") (part "TCRT5000"))
    )
    (comp (ref "TCRT_29")
      (value "TCRT5000")
      (footprint "eagle-import:TCRT5000")
      (libsource (lib "eagle-import") (part "TCRT5000"))
    )
    (comp (ref "TCRT_30")
      (value "TCRT5000")
      (footprint "eagle-import:TCRT5000")
      (libsource (lib "eagle-import") (part "TCRT5000"))
    )
    (comp (ref "TP1")
      (value "PTR1TP20R")
      (footprint "eagle-import:TP20R")
      (libsource (lib "eagle-import") (part "PTR1TP20R"))
    )
    (comp (ref "TP2")
      (value "PTR1TP20R")
      (footprint "eagle-import:TP20R")
      (libsource (lib "eagle-import") (part "PTR1TP20R"))
    )
    (comp (ref "TP3")
      (value "PTR1TP20R")
      (footprint "eagle-import:TP20R")
      (libsource (lib "eagle-import") (part "PTR1TP20R"))
    )
    (comp (ref "TP4")
      (value "PTR1TP20R")
      (footprint "eagle-import:TP20R")
      (libsource (lib "eagle-import") (part "PTR1TP20R"))
    )
    (comp (ref "TP5")
      (value "PTR1TP20R")
      (footprint "eagle-import:TP20R")
      (libsource (lib "eagle-import") (part "PTR1TP20R"))
    )
    (comp (ref "TP6")
      (value "PTR1TP20R")
      (footprint "eagle-import:TP20R")
      (libsource (lib "eagle-import") (part "PTR1TP20R"))
    )
    (comp (ref "TP7")
      (value "PTR1TP20R")
      (footprint "eagle-import:TP20R")
      (libsource (lib "eagle-import") (part "PTR1TP20R"))
    )
    (comp (ref "TP8")
      (value "PTR1TP20R")
      (footprint "eagle-import:TP20R")
      (libsource (lib "eagle-import") (part "PTR1TP20R"))
    )
    (comp (ref "TP9")
      (value "PTR1TP20R")
      (footprint "eagle-import:TP20R")
      (libsource (lib "eagle-import") (part "PTR1TP20R"))
    )
    (comp (ref "TP10")
      (value "PTR1TP20R")
      (footprint "eagle-import:TP20R")
      (libsource (lib "eagle-import") (part "PTR1TP20R"))
    )
    (comp (ref "TP11")
      (value "PTR1TP20R")
      (footprint "eagle-import:TP20R")
      (libsource (lib "eagle-import") (part "PTR1TP20R"))
    )
    (comp (ref "TP12")
      (value "PTR1TP20R")
      (footprint "eagle-import:TP20R")
      (libsource (lib "eagle-import") (part "PTR1TP20R"))
    )
    (comp (ref "TP13")
      (value "PTR1TP20R")
      (footprint "eagle-import:TP20R")
      (libsource (lib "eagle-import") (part "PTR1TP20R"))
    )
    (comp (ref "TP14")
      (value "PTR1TP20R")
      (footprint "eagle-import:TP20R")
      (libsource (lib "eagle-import") (part "PTR1TP20R"))
    )
    (comp (ref "TP15")
      (value "PTR1TP20R")
      (footprint "eagle-import:TP20R")
      (libsource (lib "eagle-import") (part "PTR1TP20R"))
    )
    (comp (ref "TP16")
      (value "PTR1TP20R")
      (footprint "eagle-import:TP20R")
      (libsource (lib "eagle-import") (part "PTR1TP20R"))
    )
    (comp (ref "TP17")
      (value "PTR1TP20R")
      (footprint "eagle-import:TP20R")
      (libsource (lib "eagle-import") (part "PTR1TP20R"))
    )
    (comp (ref "TP18")
      (value "PTR1TP20R")
      (footprint "eagle-import:TP20R")
      (libsource (lib "eagle-import") (part "PTR1TP20R"))
    )
    (comp (ref "TP19")
      (value "PTR1TP20R")
      (footprint "eagle-import:TP20R")
      (libsource (lib "eagle-import") (part "PTR1TP20R"))
    )
    (comp (ref "TP20")
      (value "PTR1TP20R")
      (footprint "eagle-import:TP20R")
      (libsource (lib "eagle-import") (part "PTR1TP20R"))
    )
    (comp (ref "TP21")
      (value "PTR1TP20R")
      (footprint "eagle-import:TP20R")
      (libsource (lib "eagle-import") (part "PTR1TP20R"))
    )
    (comp (ref "TP22")
      (value "PTR1TP20R")
      (footprint "eagle-import:TP20R")
      (libsource (lib "eagle-import") (part "PTR1TP20R"))
    )
    (comp (ref "TP23")
      (value "PTR1TP20R")
      (footprint "eagle-import:TP20R")
      (libsource (lib "eagle-import") (part "PTR1TP20R"))
    )
    (comp (ref "TRIM")
      (value "3362W-1-103LF")
      (footprint "eagle-import:POT_3362W")
      (libsource (lib "eagle-import") (part "3362W-1-103LF"))
    )
    (comp (ref "U$1")
      (value "0603_S")
      (footprint "eagle-import:0603_S")
      (libsource (lib "eagle-import") (part "0603_S"))
    )
    (comp (ref "U$2")
      (value "0603_S")
      (footprint "eagle-import:0603_S")
      (libsource (lib "eagle-import") (part "0603_S"))
    )
    (comp (ref "U$3")
      (value "0603_S")
      (footprint "eagle-import:0603_S")
      (libsource (lib "eagle-import") (part "0603_S"))
    )
    (comp (ref "U1")
      (value "AT28BV25628T_ATM-M")
      (footprint "eagle-import:28T_ATM-M")
      (fields (field (name "MANUFACTURER_PART_NUMBER") "AT28BV256-20TU"))
      (libsource (lib "eagle-import") (part "AT28BV25628T_ATM-M"))
    )
    (comp (ref "U2")
      (value "1049P")
      (footprint "eagle-import:1049P")
      (fields (field (name "MOUSER_PART_NUMBER") "534-1049P"))
      (libsource (lib "eagle-import") (part "1049P"))
    )
    (comp (ref "U3")
      (value "1049P")
      (footprint "eagle-import:1049P")
      (fields (field (name "MOUSER_PART_NUMBER") "534-1049P"))
      (libsource (lib "eagle-import") (part "1049P"))
    )
    (comp (ref "X1")
      (value "ML2\"")
      (footprint "eagle-import:ML2")
      (libsource (lib "eagle-import") (part "ML2{dblquote}"))
    )
    (comp (ref "X2")
      (value "ML2\"")
      (footprint "eagle-import:ML2")
      (libsource (lib "eagle-import") (part "ML2{dblquote}"))
    )
    (comp (ref "Z1")
      (value "1n5824")
      (footprint "eagle-import:SUPRESSOR_SMAJ")
      (libsource (lib "eagle-import") (part "SUPRESSOR_TVS-UD-SMAJ"))
    )
    (comp (ref "Z2")
      (value "1n5824")
      (footprint "eagle-import:SUPRESSOR_SMAJ")
      (libsource (lib "eagle-import") (part "SUPRESSOR_TVS-UD-SMAJ"))
    )
  )
  (nets
    (net (code "1") (name "/~{CE}") (class "Default")
      (node (ref "U$3") (pin "2") (pinfunction "A2_2") (pintype "bidirectional"))
      (node (ref "U1") (pin "27") (pinfunction "~{CE}_27") (pintype "passive"))
    )
    (net (code "2") (name "/~{OE}") (class "Default")
      (node (ref "U$2") (pin "2") (pinfunction "A2_2") (pintype "bidirectional"))
      (node (ref "U1") (pin "1") (pinfunction "~{OE}_1") (pintype "output"))
    )
    (net (code "3") (name "/~{WE}") (class "Default")
      (node (ref "U$1") (pin "2") (pinfunction "A2_2") (pintype "bidirectional"))
      (node (ref "U1") (pin "6") (pinfunction "~{WE}_6") (pintype "passive"))
    )
    (net (code "4") (name "3.3V") (class "Default")
      (node (ref "C43") (pin "1") (pinfunction "1_1") (pintype "passive"))
      (node (ref "C44") (pin "1") (pinfunction "1_1") (pintype "passive"))
      (node (ref "C48") (pin "1") (pinfunction "1_1") (pintype "passive"))
      (node (ref "IC1") (pin "10") (pinfunction "OE_10") (pintype "bidirectional"))
      (node (ref "IC1") (pin "2") (pinfunction "VCCA_2") (pintype "bidirectional"))
      (node (ref "IC2") (pin "2") (pinfunction "VOUT_2") (pintype "output"))
      (node (ref "Q1") (pin "1") (pinfunction "G_1") (pintype "passive"))
      (node (ref "R73") (pin "1") (pinfunction "1_1") (pintype "passive"))
      (node (ref "SV1") (pin "28") (pinfunction "28_28") (pintype "passive"))
    )
    (net (code "5") (name "5V") (class "Default")
      (node (ref "C10") (pin "1") (pinfunction "1_1") (pintype "passive"))
      (node (ref "C11") (pin "1") (pinfunction "1_1") (pintype "passive"))
      (node (ref "C12") (pin "1") (pinfunction "1_1") (pintype "passive"))
      (node (ref "C13") (pin "1") (pinfunction "1_1") (pintype "passive"))
      (node (ref "C14") (pin "1") (pinfunction "1_1") (pintype "passive"))
      (node (ref "C15") (pin "1") (pinfunction "1_1") (pintype "passive"))
      (node (ref "C16") (pin "1") (pinfunction "1_1") (pintype "passive"))
      (node (ref "C17") (pin "1") (pinfunction "1_1") (pintype "passive"))
      (node (ref "C18") (pin "1") (pinfunction "1_1") (pintype "passive"))
      (node (ref "C19") (pin "1") (pinfunction "1_1") (pintype "passive"))
      (node (ref "C2") (pin "1") (pinfunction "1_1") (pintype "passive"))
      (node (ref "C20") (pin "1") (pinfunction "1_1") (pintype "passive"))
      (node (ref "C21") (pin "1") (pinfunction "1_1") (pintype "passive"))
      (node (ref "C22") (pin "1") (pinfunction "1_1") (pintype "passive"))
      (node (ref "C23") (pin "1") (pinfunction "1_1") (pintype "passive"))
      (node (ref "C24") (pin "1") (pinfunction "1_1") (pintype "passive"))
      (node (ref "C25") (pin "1") (pinfunction "1_1") (pintype "passive"))
      (node (ref "C26") (pin "1") (pinfunction "1_1") (pintype "passive"))
      (node (ref "C27") (pin "1") (pinfunction "1_1") (pintype "passive"))
      (node (ref "C28") (pin "1") (pinfunction "1_1") (pintype "passive"))
      (node (ref "C29") (pin "1") (pinfunction "1_1") (pintype "passive"))
      (node (ref "C3") (pin "1") (pinfunction "1_1") (pintype "passive"))
      (node (ref "C30") (pin "1") (pinfunction "1_1") (pintype "passive"))
      (node (ref "C31") (pin "1") (pinfunction "1_1") (pintype "passive"))
      (node (ref "C32") (pin "1") (pinfunction "1_1") (pintype "passive"))
      (node (ref "C33") (pin "1") (pinfunction "1_1") (pintype "passive"))
      (node (ref "C34") (pin "1") (pinfunction "1_1") (pintype "passive"))
      (node (ref "C35") (pin "1") (pinfunction "1_1") (pintype "passive"))
      (node (ref "C36") (pin "1") (pinfunction "1_1") (pintype "passive"))
      (node (ref "C37") (pin "1") (pinfunction "1_1") (pintype "passive"))
      (node (ref "C38") (pin "1") (pinfunction "1_1") (pintype "passive"))
      (node (ref "C39") (pin "1") (pinfunction "1_1") (pintype "passive"))
      (node (ref "C40") (pin "1") (pinfunction "1_1") (pintype "passive"))
      (node (ref "C41") (pin "1") (pinfunction "1_1") (pintype "passive"))
      (node (ref "C42") (pin "1") (pinfunction "1_1") (pintype "passive"))
      (node (ref "C47") (pin "1") (pinfunction "1_1") (pintype "passive"))
      (node (ref "C51") (pin "1") (pinfunction "1_1") (pintype "passive"))
      (node (ref "C7") (pin "1") (pinfunction "1_1") (pintype "passive"))
      (node (ref "C8") (pin "1") (pinfunction "1_1") (pintype "passive"))
      (node (ref "C9") (pin "1") (pinfunction "1_1") (pintype "passive"))
      (node (ref "COMP_1") (pin "5") (pinfunction "5_5") (pintype "passive"))
      (node (ref "COMP_10") (pin "5") (pinfunction "5_5") (pintype "passive"))
      (node (ref "COMP_11") (pin "5") (pinfunction "5_5") (pintype "passive"))
      (node (ref "COMP_12") (pin "5") (pinfunction "5_5") (pintype "passive"))
      (node (ref "COMP_13") (pin "5") (pinfunction "5_5") (pintype "passive"))
      (node (ref "COMP_14") (pin "5") (pinfunction "5_5") (pintype "passive"))
      (node (ref "COMP_15") (pin "5") (pinfunction "5_5") (pintype "passive"))
      (node (ref "COMP_16") (pin "5") (pinfunction "5_5") (pintype "passive"))
      (node (ref "COMP_17") (pin "5") (pinfunction "5_5") (pintype "passive"))
      (node (ref "COMP_18") (pin "5") (pinfunction "5_5") (pintype "passive"))
      (node (ref "COMP_19") (pin "5") (pinfunction "5_5") (pintype "passive"))
      (node (ref "COMP_2") (pin "5") (pinfunction "5_5") (pintype "passive"))
      (node (ref "COMP_20") (pin "5") (pinfunction "5_5") (pintype "passive"))
      (node (ref "COMP_21") (pin "5") (pinfunction "5_5") (pintype "passive"))
      (node (ref "COMP_22") (pin "5") (pinfunction "5_5") (pintype "passive"))
      (node (ref "COMP_23") (pin "5") (pinfunction "5_5") (pintype "passive"))
      (node (ref "COMP_24") (pin "5") (pinfunction "5_5") (pintype "passive"))
      (node (ref "COMP_25") (pin "5") (pinfunction "5_5") (pintype "passive"))
      (node (ref "COMP_26") (pin "5") (pinfunction "5_5") (pintype "passive"))
      (node (ref "COMP_27") (pin "5") (pinfunction "5_5") (pintype "passive"))
      (node (ref "COMP_28") (pin "5") (pinfunction "5_5") (pintype "passive"))
      (node (ref "COMP_29") (pin "5") (pinfunction "5_5") (pintype "passive"))
      (node (ref "COMP_3") (pin "5") (pinfunction "5_5") (pintype "passive"))
      (node (ref "COMP_30") (pin "5") (pinfunction "5_5") (pintype "passive"))
      (node (ref "COMP_4") (pin "5") (pinfunction "5_5") (pintype "passive"))
      (node (ref "COMP_5") (pin "5") (pinfunction "5_5") (pintype "passive"))
      (node (ref "COMP_6") (pin "5") (pinfunction "5_5") (pintype "passive"))
      (node (ref "COMP_7") (pin "5") (pinfunction "5_5") (pintype "passive"))
      (node (ref "COMP_8") (pin "5") (pinfunction "5_5") (pintype "passive"))
      (node (ref "COMP_9") (pin "5") (pinfunction "5_5") (pintype "passive"))
      (node (ref "IC1") (pin "19") (pinfunction "VCCB_19") (pintype "bidirectional"))
      (node (ref "IO2") (pin "4") (pinfunction "FB_4") (pintype "input"))
      (node (ref "L2") (pin "2") (pinfunction "2_2") (pintype "passive"))
      (node (ref "OR_1") (pin "14") (pinfunction "VCC_14") (pintype "power_in"))
      (node (ref "OR_2") (pin "14") (pinfunction "VCC_14") (pintype "power_in"))
      (node (ref "OR_3") (pin "14") (pinfunction "VCC_14") (pintype "power_in"))
      (node (ref "OR_4") (pin "14") (pinfunction "VCC_14") (pintype "power_in"))
      (node (ref "OR_5") (pin "14") (pinfunction "VCC_14") (pintype "power_in"))
      (node (ref "OR_6") (pin "14") (pinfunction "VCC_14") (pintype "power_in"))
      (node (ref "R77") (pin "1") (pinfunction "1_1") (pintype "passive"))
      (node (ref "TCRT_1") (pin "A") (pinfunction "ANODE_A") (pintype "passive"))
      (node (ref "TCRT_1") (pin "C") (pinfunction "COLLECTOR_C") (pintype "passive"))
      (node (ref "TCRT_10") (pin "A") (pinfunction "ANODE_A") (pintype "passive"))
      (node (ref "TCRT_10") (pin "C") (pinfunction "COLLECTOR_C") (pintype "passive"))
      (node (ref "TCRT_11") (pin "A") (pinfunction "ANODE_A") (pintype "passive"))
      (node (ref "TCRT_11") (pin "C") (pinfunction "COLLECTOR_C") (pintype "passive"))
      (node (ref "TCRT_12") (pin "A") (pinfunction "ANODE_A") (pintype "passive"))
      (node (ref "TCRT_12") (pin "C") (pinfunction "COLLECTOR_C") (pintype "passive"))
      (node (ref "TCRT_13") (pin "A") (pinfunction "ANODE_A") (pintype "passive"))
      (node (ref "TCRT_13") (pin "C") (pinfunction "COLLECTOR_C") (pintype "passive"))
      (node (ref "TCRT_14") (pin "A") (pinfunction "ANODE_A") (pintype "passive"))
      (node (ref "TCRT_14") (pin "C") (pinfunction "COLLECTOR_C") (pintype "passive"))
      (node (ref "TCRT_15") (pin "A") (pinfunction "ANODE_A") (pintype "passive"))
      (node (ref "TCRT_15") (pin "C") (pinfunction "COLLECTOR_C") (pintype "passive"))
      (node (ref "TCRT_16") (pin "A") (pinfunction "ANODE_A") (pintype "passive"))
      (node (ref "TCRT_16") (pin "C") (pinfunction "COLLECTOR_C") (pintype "passive"))
      (node (ref "TCRT_17") (pin "A") (pinfunction "ANODE_A") (pintype "passive"))
      (node (ref "TCRT_17") (pin "C") (pinfunction "COLLECTOR_C") (pintype "passive"))
      (node (ref "TCRT_18") (pin "A") (pinfunction "ANODE_A") (pintype "passive"))
      (node (ref "TCRT_18") (pin "C") (pinfunction "COLLECTOR_C") (pintype "passive"))
      (node (ref "TCRT_19") (pin "A") (pinfunction "ANODE_A") (pintype "passive"))
      (node (ref "TCRT_19") (pin "C") (pinfunction "COLLECTOR_C") (pintype "passive"))
      (node (ref "TCRT_2") (pin "A") (pinfunction "ANODE_A") (pintype "passive"))
      (node (ref "TCRT_2") (pin "C") (pinfunction "COLLECTOR_C") (pintype "passive"))
      (node (ref "TCRT_20") (pin "A") (pinfunction "ANODE_A") (pintype "passive"))
      (node (ref "TCRT_20") (pin "C") (pinfunction "COLLECTOR_C") (pintype "passive"))
      (node (ref "TCRT_21") (pin "A") (pinfunction "ANODE_A") (pintype "passive"))
      (node (ref "TCRT_21") (pin "C") (pinfunction "COLLECTOR_C") (pintype "passive"))
      (node (ref "TCRT_22") (pin "A") (pinfunction "ANODE_A") (pintype "passive"))
      (node (ref "TCRT_22") (pin "C") (pinfunction "COLLECTOR_C") (pintype "passive"))
      (node (ref "TCRT_23") (pin "A") (pinfunction "ANODE_A") (pintype "passive"))
      (node (ref "TCRT_23") (pin "C") (pinfunction "COLLECTOR_C") (pintype "passive"))
      (node (ref "TCRT_24") (pin "A") (pinfunction "ANODE_A") (pintype "passive"))
      (node (ref "TCRT_24") (pin "C") (pinfunction "COLLECTOR_C") (pintype "passive"))
      (node (ref "TCRT_25") (pin "A") (pinfunction "ANODE_A") (pintype "passive"))
      (node (ref "TCRT_25") (pin "C") (pinfunction "COLLECTOR_C") (pintype "passive"))
      (node (ref "TCRT_26") (pin "A") (pinfunction "ANODE_A") (pintype "passive"))
      (node (ref "TCRT_26") (pin "C") (pinfunction "COLLECTOR_C") (pintype "passive"))
      (node (ref "TCRT_27") (pin "A") (pinfunction "ANODE_A") (pintype "passive"))
      (node (ref "TCRT_27") (pin "C") (pinfunction "COLLECTOR_C") (pintype "passive"))
      (node (ref "TCRT_28") (pin "A") (pinfunction "ANODE_A") (pintype "passive"))
      (node (ref "TCRT_28") (pin "C") (pinfunction "COLLECTOR_C") (pintype "passive"))
      (node (ref "TCRT_29") (pin "A") (pinfunction "ANODE_A") (pintype "passive"))
      (node (ref "TCRT_29") (pin "C") (pinfunction "COLLECTOR_C") (pintype "passive"))
      (node (ref "TCRT_3") (pin "A") (pinfunction "ANODE_A") (pintype "passive"))
      (node (ref "TCRT_3") (pin "C") (pinfunction "COLLECTOR_C") (pintype "passive"))
      (node (ref "TCRT_30") (pin "A") (pinfunction "ANODE_A") (pintype "passive"))
      (node (ref "TCRT_30") (pin "C") (pinfunction "COLLECTOR_C") (pintype "passive"))
      (node (ref "TCRT_4") (pin "A") (pinfunction "ANODE_A") (pintype "passive"))
      (node (ref "TCRT_4") (pin "C") (pinfunction "COLLECTOR_C") (pintype "passive"))
      (node (ref "TCRT_5") (pin "A") (pinfunction "ANODE_A") (pintype "passive"))
      (node (ref "TCRT_5") (pin "C") (pinfunction "COLLECTOR_C") (pintype "passive"))
      (node (ref "TCRT_6") (pin "A") (pinfunction "ANODE_A") (pintype "passive"))
      (node (ref "TCRT_6") (pin "C") (pinfunction "COLLECTOR_C") (pintype "passive"))
      (node (ref "TCRT_7") (pin "A") (pinfunction "ANODE_A") (pintype "passive"))
      (node (ref "TCRT_7") (pin "C") (pinfunction "COLLECTOR_C") (pintype "passive"))
      (node (ref "TCRT_8") (pin "A") (pinfunction "ANODE_A") (pintype "passive"))
      (node (ref "TCRT_8") (pin "C") (pinfunction "COLLECTOR_C") (pintype "passive"))
      (node (ref "TCRT_9") (pin "A") (pinfunction "ANODE_A") (pintype "passive"))
      (node (ref "TCRT_9") (pin "C") (pinfunction "COLLECTOR_C") (pintype "passive"))
      (node (ref "TRIM") (pin "3") (pinfunction "3_3") (pintype "passive"))
      (node (ref "U$1") (pin "3") (pinfunction "A3_3") (pintype "bidirectional"))
      (node (ref "U$2") (pin "3") (pinfunction "A3_3") (pintype "bidirectional"))
      (node (ref "U$3") (pin "3") (pinfunction "A3_3") (pintype "bidirectional"))
      (node (ref "U1") (pin "7") (pinfunction "VCC_7") (pintype "power_in"))
    )
    (net (code "6") (name "5V_JATSON") (class "Default")
      (node (ref "C4") (pin "1") (pinfunction "1_1") (pintype "passive"))
      (node (ref "C6") (pin "1") (pinfunction "1_1") (pintype "passive"))
      (node (ref "IO1") (pin "4") (pinfunction "FB_4") (pintype "input"))
      (node (ref "L1") (pin "2") (pinfunction "2_2") (pintype "passive"))
      (node (ref "SV1") (pin "22") (pinfunction "22_22") (pintype "passive"))
      (node (ref "SV1") (pin "24") (pinfunction "24_24") (pintype "passive"))
      (node (ref "SV1") (pin "26") (pinfunction "26_26") (pintype "passive"))
    )
    (net (code "7") (name "A0") (class "Default")
      (node (ref "R63") (pin "1") (pinfunction "1_1") (pintype "passive"))
      (node (ref "TP4") (pin "TP") (pinfunction "TP_TP") (pintype "input"))
      (node (ref "U1") (pin "17") (pinfunction "A0_17") (pintype "passive"))
    )
    (net (code "8") (name "A1") (class "Default")
      (node (ref "R64") (pin "1") (pinfunction "1_1") (pintype "passive"))
      (node (ref "TP3") (pin "TP") (pinfunction "TP_TP") (pintype "input"))
      (node (ref "U1") (pin "16") (pinfunction "A1_16") (pintype "passive"))
    )
    (net (code "9") (name "A2") (class "Default")
      (node (ref "R62") (pin "1") (pinfunction "1_1") (pintype "passive"))
      (node (ref "TP1") (pin "TP") (pinfunction "TP_TP") (pintype "input"))
      (node (ref "U1") (pin "15") (pinfunction "A2_15") (pintype "passive"))
    )
    (net (code "10") (name "A3") (class "Default")
      (node (ref "R61") (pin "1") (pinfunction "1_1") (pintype "passive"))
      (node (ref "TP2") (pin "TP") (pinfunction "TP_TP") (pintype "input"))
      (node (ref "U1") (pin "14") (pinfunction "A3_14") (pintype "passive"))
    )
    (net (code "11") (name "A4") (class "Default")
      (node (ref "R68") (pin "1") (pinfunction "1_1") (pintype "passive"))
      (node (ref "TP7") (pin "TP") (pinfunction "TP_TP") (pintype "input"))
      (node (ref "U1") (pin "13") (pinfunction "A4_13") (pintype "passive"))
    )
    (net (code "12") (name "A5") (class "Default")
      (node (ref "R67") (pin "1") (pinfunction "1_1") (pintype "passive"))
      (node (ref "TP8") (pin "TP") (pinfunction "TP_TP") (pintype "input"))
      (node (ref "U1") (pin "12") (pinfunction "A5_12") (pintype "passive"))
    )
    (net (code "13") (name "A6") (class "Default")
      (node (ref "R66") (pin "1") (pinfunction "1_1") (pintype "passive"))
      (node (ref "TP5") (pin "TP") (pinfunction "TP_TP") (pintype "input"))
      (node (ref "U1") (pin "11") (pinfunction "A6_11") (pintype "passive"))
    )
    (net (code "14") (name "A7") (class "Default")
      (node (ref "R65") (pin "1") (pinfunction "1_1") (pintype "passive"))
      (node (ref "TP6") (pin "TP") (pinfunction "TP_TP") (pintype "input"))
      (node (ref "U1") (pin "10") (pinfunction "A7_10") (pintype "passive"))
    )
    (net (code "15") (name "A8") (class "Default")
      (node (ref "R72") (pin "1") (pinfunction "1_1") (pintype "passive"))
      (node (ref "TP11") (pin "TP") (pinfunction "TP_TP") (pintype "input"))
      (node (ref "U1") (pin "4") (pinfunction "A8_4") (pintype "passive"))
    )
    (net (code "16") (name "A9") (class "Default")
      (node (ref "R71") (pin "1") (pinfunction "1_1") (pintype "passive"))
      (node (ref "TP12") (pin "TP") (pinfunction "TP_TP") (pintype "input"))
      (node (ref "U1") (pin "3") (pinfunction "A9_3") (pintype "passive"))
    )
    (net (code "17") (name "A10") (class "Default")
      (node (ref "R70") (pin "1") (pinfunction "1_1") (pintype "passive"))
      (node (ref "TP9") (pin "TP") (pinfunction "TP_TP") (pintype "input"))
      (node (ref "U1") (pin "28") (pinfunction "A10_28") (pintype "passive"))
    )
    (net (code "18") (name "A11") (class "Default")
      (node (ref "R69") (pin "1") (pinfunction "1_1") (pintype "passive"))
      (node (ref "TP10") (pin "TP") (pinfunction "TP_TP") (pintype "input"))
      (node (ref "U1") (pin "2") (pinfunction "A11_2") (pintype "passive"))
    )
    (net (code "19") (name "A12") (class "Default")
      (node (ref "R76") (pin "1") (pinfunction "1_1") (pintype "passive"))
      (node (ref "TP15") (pin "TP") (pinfunction "TP_TP") (pintype "input"))
      (node (ref "U1") (pin "9") (pinfunction "A12_9") (pintype "passive"))
    )
    (net (code "20") (name "A13") (class "Default")
      (node (ref "R75") (pin "1") (pinfunction "1_1") (pintype "passive"))
      (node (ref "TP16") (pin "TP") (pinfunction "TP_TP") (pintype "input"))
      (node (ref "U1") (pin "5") (pinfunction "A13_5") (pintype "passive"))
    )
    (net (code "21") (name "A14") (class "Default")
      (node (ref "R74") (pin "1") (pinfunction "1_1") (pintype "passive"))
      (node (ref "TP13") (pin "TP") (pinfunction "TP_TP") (pintype "input"))
      (node (ref "U1") (pin "8") (pinfunction "A14_8") (pintype "passive"))
    )
    (net (code "22") (name "BAT") (class "Default")
      (node (ref "C1") (pin "1") (pinfunction "1_1") (pintype "passive"))
      (node (ref "C45") (pin "1") (pinfunction "1_1") (pintype "passive"))
      (node (ref "C46") (pin "1") (pinfunction "1_1") (pintype "passive"))
      (node (ref "C5") (pin "1") (pinfunction "1_1") (pintype "passive"))
      (node (ref "IC2") (pin "3") (pinfunction "VIN_3") (pintype "input"))
      (node (ref "IO1") (pin "1") (pinfunction "IN_1") (pintype "input"))
      (node (ref "IO2") (pin "1") (pinfunction "IN_1") (pintype "input"))
      (node (ref "MAIN_POWER") (pin "3") (pinfunction "3-ON_3") (pintype "passive"))
    )
    (net (code "23") (name "BAT_UP") (class "Default")
      (node (ref "FUSE1") (pin "1") (pinfunction "1_1") (pintype "passive"))
      (node (ref "SV1") (pin "10") (pinfunction "10_10") (pintype "passive"))
      (node (ref "SV1") (pin "12") (pinfunction "12_12") (pintype "passive"))
      (node (ref "SV1") (pin "14") (pinfunction "14_14") (pintype "passive"))
      (node (ref "SV1") (pin "16") (pinfunction "16_16") (pintype "passive"))
      (node (ref "SV1") (pin "18") (pinfunction "18_18") (pintype "passive"))
      (node (ref "SV1") (pin "2") (pinfunction "2_2") (pintype "passive"))
      (node (ref "SV1") (pin "20") (pinfunction "20_20") (pintype "passive"))
      (node (ref "SV1") (pin "4") (pinfunction "4_4") (pintype "passive"))
      (node (ref "SV1") (pin "6") (pinfunction "6_6") (pintype "passive"))
      (node (ref "SV1") (pin "8") (pinfunction "8_8") (pintype "passive"))
    )
    (net (code "24") (name "CAPACITOR") (class "Default")
      (node (ref "Q3") (pin "G") (pinfunction "G_G") (pintype "passive"))
      (node (ref "R79") (pin "2") (pinfunction "2_2") (pintype "passive"))
      (node (ref "SV1") (pin "30") (pinfunction "30_30") (pintype "passive"))
    )
    (net (code "25") (name "GND") (class "Default")
      (node (ref "C1") (pin "2") (pinfunction "2_2") (pintype "passive"))
      (node (ref "C10") (pin "2") (pinfunction "2_2") (pintype "passive"))
      (node (ref "C11") (pin "2") (pinfunction "2_2") (pintype "passive"))
      (node (ref "C12") (pin "2") (pinfunction "2_2") (pintype "passive"))
      (node (ref "C13") (pin "2") (pinfunction "2_2") (pintype "passive"))
      (node (ref "C14") (pin "2") (pinfunction "2_2") (pintype "passive"))
      (node (ref "C15") (pin "2") (pinfunction "2_2") (pintype "passive"))
      (node (ref "C16") (pin "2") (pinfunction "2_2") (pintype "passive"))
      (node (ref "C17") (pin "2") (pinfunction "2_2") (pintype "passive"))
      (node (ref "C18") (pin "2") (pinfunction "2_2") (pintype "passive"))
      (node (ref "C19") (pin "2") (pinfunction "2_2") (pintype "passive"))
      (node (ref "C2") (pin "2") (pinfunction "2_2") (pintype "passive"))
      (node (ref "C20") (pin "2") (pinfunction "2_2") (pintype "passive"))
      (node (ref "C21") (pin "2") (pinfunction "2_2") (pintype "passive"))
      (node (ref "C22") (pin "2") (pinfunction "2_2") (pintype "passive"))
      (node (ref "C23") (pin "2") (pinfunction "2_2") (pintype "passive"))
      (node (ref "C24") (pin "2") (pinfunction "2_2") (pintype "passive"))
      (node (ref "C25") (pin "2") (pinfunction "2_2") (pintype "passive"))
      (node (ref "C26") (pin "2") (pinfunction "2_2") (pintype "passive"))
      (node (ref "C27") (pin "2") (pinfunction "2_2") (pintype "passive"))
      (node (ref "C28") (pin "2") (pinfunction "2_2") (pintype "passive"))
      (node (ref "C29") (pin "2") (pinfunction "2_2") (pintype "passive"))
      (node (ref "C3") (pin "2") (pinfunction "2_2") (pintype "passive"))
      (node (ref "C30") (pin "2") (pinfunction "2_2") (pintype "passive"))
      (node (ref "C31") (pin "2") (pinfunction "2_2") (pintype "passive"))
      (node (ref "C32") (pin "2") (pinfunction "2_2") (pintype "passive"))
      (node (ref "C33") (pin "2") (pinfunction "2_2") (pintype "passive"))
      (node (ref "C34") (pin "2") (pinfunction "2_2") (pintype "passive"))
      (node (ref "C35") (pin "2") (pinfunction "2_2") (pintype "passive"))
      (node (ref "C36") (pin "2") (pinfunction "2_2") (pintype "passive"))
      (node (ref "C37") (pin "2") (pinfunction "2_2") (pintype "passive"))
      (node (ref "C38") (pin "2") (pinfunction "2_2") (pintype "passive"))
      (node (ref "C39") (pin "2") (pinfunction "2_2") (pintype "passive"))
      (node (ref "C4") (pin "2") (pinfunction "2_2") (pintype "passive"))
      (node (ref "C40") (pin "2") (pinfunction "2_2") (pintype "passive"))
      (node (ref "C41") (pin "2") (pinfunction "2_2") (pintype "passive"))
      (node (ref "C42") (pin "2") (pinfunction "2_2") (pintype "passive"))
      (node (ref "C43") (pin "2") (pinfunction "2_2") (pintype "passive"))
      (node (ref "C44") (pin "2") (pinfunction "2_2") (pintype "passive"))
      (node (ref "C45") (pin "2") (pinfunction "2_2") (pintype "passive"))
      (node (ref "C46") (pin "2") (pinfunction "2_2") (pintype "passive"))
      (node (ref "C47") (pin "2") (pinfunction "2_2") (pintype "passive"))
      (node (ref "C48") (pin "2") (pinfunction "2_2") (pintype "passive"))
      (node (ref "C49") (pin "-") (pinfunction "-_-") (pintype "passive"))
      (node (ref "C5") (pin "2") (pinfunction "2_2") (pintype "passive"))
      (node (ref "C50") (pin "-") (pinfunction "-_-") (pintype "passive"))
      (node (ref "C51") (pin "2") (pinfunction "2_2") (pintype "passive"))
      (node (ref "C52") (pin "1") (pinfunction "1_1") (pintype "passive"))
      (node (ref "C6") (pin "2") (pinfunction "2_2") (pintype "passive"))
      (node (ref "C7") (pin "2") (pinfunction "2_2") (pintype "passive"))
      (node (ref "C8") (pin "2") (pinfunction "2_2") (pintype "passive"))
      (node (ref "C9") (pin "2") (pinfunction "2_2") (pintype "passive"))
      (node (ref "COMP_1") (pin "2") (pinfunction "2_2") (pintype "passive"))
      (node (ref "COMP_10") (pin "2") (pinfunction "2_2") (pintype "passive"))
      (node (ref "COMP_11") (pin "2") (pinfunction "2_2") (pintype "passive"))
      (node (ref "COMP_12") (pin "2") (pinfunction "2_2") (pintype "passive"))
      (node (ref "COMP_13") (pin "2") (pinfunction "2_2") (pintype "passive"))
      (node (ref "COMP_14") (pin "2") (pinfunction "2_2") (pintype "passive"))
      (node (ref "COMP_15") (pin "2") (pinfunction "2_2") (pintype "passive"))
      (node (ref "COMP_16") (pin "2") (pinfunction "2_2") (pintype "passive"))
      (node (ref "COMP_17") (pin "2") (pinfunction "2_2") (pintype "passive"))
      (node (ref "COMP_18") (pin "2") (pinfunction "2_2") (pintype "passive"))
      (node (ref "COMP_19") (pin "2") (pinfunction "2_2") (pintype "passive"))
      (node (ref "COMP_2") (pin "2") (pinfunction "2_2") (pintype "passive"))
      (node (ref "COMP_20") (pin "2") (pinfunction "2_2") (pintype "passive"))
      (node (ref "COMP_21") (pin "2") (pinfunction "2_2") (pintype "passive"))
      (node (ref "COMP_22") (pin "2") (pinfunction "2_2") (pintype "passive"))
      (node (ref "COMP_23") (pin "2") (pinfunction "2_2") (pintype "passive"))
      (node (ref "COMP_24") (pin "2") (pinfunction "2_2") (pintype "passive"))
      (node (ref "COMP_25") (pin "2") (pinfunction "2_2") (pintype "passive"))
      (node (ref "COMP_26") (pin "2") (pinfunction "2_2") (pintype "passive"))
      (node (ref "COMP_27") (pin "2") (pinfunction "2_2") (pintype "passive"))
      (node (ref "COMP_28") (pin "2") (pinfunction "2_2") (pintype "passive"))
      (node (ref "COMP_29") (pin "2") (pinfunction "2_2") (pintype "passive"))
      (node (ref "COMP_3") (pin "2") (pinfunction "2_2") (pintype "passive"))
      (node (ref "COMP_30") (pin "2") (pinfunction "2_2") (pintype "passive"))
      (node (ref "COMP_4") (pin "2") (pinfunction "2_2") (pintype "passive"))
      (node (ref "COMP_5") (pin "2") (pinfunction "2_2") (pintype "passive"))
      (node (ref "COMP_6") (pin "2") (pinfunction "2_2") (pintype "passive"))
      (node (ref "COMP_7") (pin "2") (pinfunction "2_2") (pintype "passive"))
      (node (ref "COMP_8") (pin "2") (pinfunction "2_2") (pintype "passive"))
      (node (ref "COMP_9") (pin "2") (pinfunction "2_2") (pintype "passive"))
      (node (ref "IC1") (pin "11") (pinfunction "GND_11") (pintype "bidirectional"))
      (node (ref "IC2") (pin "1") (pinfunction "GND_1") (pintype "power_in"))
      (node (ref "IO1") (pin "3") (pinfunction "GND_3") (pintype "power_in"))
      (node (ref "IO1") (pin "5") (pinfunction "EN_5") (pintype "input"))
      (node (ref "IO1") (pin "6") (pinfunction "GND_6") (pintype "power_in"))
      (node (ref "IO2") (pin "3") (pinfunction "GND_3") (pintype "power_in"))
      (node (ref "IO2") (pin "5") (pinfunction "EN_5") (pintype "input"))
      (node (ref "IO2") (pin "6") (pinfunction "GND_6") (pintype "power_in"))
      (node (ref "OR_1") (pin "7") (pinfunction "GND_7") (pintype "power_in"))
      (node (ref "OR_2") (pin "7") (pinfunction "GND_7") (pintype "power_in"))
      (node (ref "OR_3") (pin "7") (pinfunction "GND_7") (pintype "power_in"))
      (node (ref "OR_4") (pin "7") (pinfunction "GND_7") (pintype "power_in"))
      (node (ref "OR_5") (pin "7") (pinfunction "GND_7") (pintype "power_in"))
      (node (ref "OR_6") (pin "7") (pinfunction "GND_7") (pintype "power_in"))
      (node (ref "R1") (pin "2") (pinfunction "2_2") (pintype "passive"))
      (node (ref "R10") (pin "2") (pinfunction "2_2") (pintype "passive"))
      (node (ref "R11") (pin "2") (pinfunction "2_2") (pintype "passive"))
      (node (ref "R12") (pin "2") (pinfunction "2_2") (pintype "passive"))
      (node (ref "R13") (pin "2") (pinfunction "2_2") (pintype "passive"))
      (node (ref "R14") (pin "2") (pinfunction "2_2") (pintype "passive"))
      (node (ref "R15") (pin "2") (pinfunction "2_2") (pintype "passive"))
      (node (ref "R16") (pin "2") (pinfunction "2_2") (pintype "passive"))
      (node (ref "R17") (pin "2") (pinfunction "2_2") (pintype "passive"))
      (node (ref "R18") (pin "2") (pinfunction "2_2") (pintype "passive"))
      (node (ref "R19") (pin "2") (pinfunction "2_2") (pintype "passive"))
      (node (ref "R2") (pin "2") (pinfunction "2_2") (pintype "passive"))
      (node (ref "R20") (pin "2") (pinfunction "2_2") (pintype "passive"))
      (node (ref "R21") (pin "2") (pinfunction "2_2") (pintype "passive"))
      (node (ref "R22") (pin "2") (pinfunction "2_2") (pintype "passive"))
      (node (ref "R23") (pin "2") (pinfunction "2_2") (pintype "passive"))
      (node (ref "R24") (pin "2") (pinfunction "2_2") (pintype "passive"))
      (node (ref "R25") (pin "2") (pinfunction "2_2") (pintype "passive"))
      (node (ref "R26") (pin "2") (pinfunction "2_2") (pintype "passive"))
      (node (ref "R27") (pin "2") (pinfunction "2_2") (pintype "passive"))
      (node (ref "R28") (pin "2") (pinfunction "2_2") (pintype "passive"))
      (node (ref "R29") (pin "2") (pinfunction "2_2") (pintype "passive"))
      (node (ref "R3") (pin "2") (pinfunction "2_2") (pintype "passive"))
      (node (ref "R30") (pin "2") (pinfunction "2_2") (pintype "passive"))
      (node (ref "R31") (pin "2") (pinfunction "2_2") (pintype "passive"))
      (node (ref "R32") (pin "2") (pinfunction "2_2") (pintype "passive"))
      (node (ref "R33") (pin "2") (pinfunction "2_2") (pintype "passive"))
      (node (ref "R34") (pin "2") (pinfunction "2_2") (pintype "passive"))
      (node (ref "R35") (pin "2") (pinfunction "2_2") (pintype "passive"))
      (node (ref "R36") (pin "2") (pinfunction "2_2") (pintype "passive"))
      (node (ref "R37") (pin "2") (pinfunction "2_2") (pintype "passive"))
      (node (ref "R38") (pin "2") (pinfunction "2_2") (pintype "passive"))
      (node (ref "R39") (pin "2") (pinfunction "2_2") (pintype "passive"))
      (node (ref "R4") (pin "2") (pinfunction "2_2") (pintype "passive"))
      (node (ref "R40") (pin "2") (pinfunction "2_2") (pintype "passive"))
      (node (ref "R41") (pin "2") (pinfunction "2_2") (pintype "passive"))
      (node (ref "R42") (pin "2") (pinfunction "2_2") (pintype "passive"))
      (node (ref "R43") (pin "2") (pinfunction "2_2") (pintype "passive"))
      (node (ref "R44") (pin "2") (pinfunction "2_2") (pintype "passive"))
      (node (ref "R45") (pin "2") (pinfunction "2_2") (pintype "passive"))
      (node (ref "R46") (pin "2") (pinfunction "2_2") (pintype "passive"))
      (node (ref "R47") (pin "2") (pinfunction "2_2") (pintype "passive"))
      (node (ref "R48") (pin "2") (pinfunction "2_2") (pintype "passive"))
      (node (ref "R49") (pin "2") (pinfunction "2_2") (pintype "passive"))
      (node (ref "R5") (pin "2") (pinfunction "2_2") (pintype "passive"))
      (node (ref "R50") (pin "2") (pinfunction "2_2") (pintype "passive"))
      (node (ref "R51") (pin "2") (pinfunction "2_2") (pintype "passive"))
      (node (ref "R52") (pin "2") (pinfunction "2_2") (pintype "passive"))
      (node (ref "R53") (pin "2") (pinfunction "2_2") (pintype "passive"))
      (node (ref "R54") (pin "2") (pinfunction "2_2") (pintype "passive"))
      (node (ref "R55") (pin "2") (pinfunction "2_2") (pintype "passive"))
      (node (ref "R56") (pin "2") (pinfunction "2_2") (pintype "passive"))
      (node (ref "R57") (pin "2") (pinfunction "2_2") (pintype "passive"))
      (node (ref "R58") (pin "2") (pinfunction "2_2") (pintype "passive"))
      (node (ref "R59") (pin "2") (pinfunction "2_2") (pintype "passive"))
      (node (ref "R6") (pin "2") (pinfunction "2_2") (pintype "passive"))
      (node (ref "R60") (pin "2") (pinfunction "2_2") (pintype "passive"))
      (node (ref "R7") (pin "2") (pinfunction "2_2") (pintype "passive"))
      (node (ref "R78") (pin "1") (pinfunction "1_1") (pintype "passive"))
      (node (ref "R79") (pin "1") (pinfunction "1_1") (pintype "passive"))
      (node (ref "R8") (pin "2") (pinfunction "2_2") (pintype "passive"))
      (node (ref "R81") (pin "2") (pinfunction "2_2") (pintype "passive"))
      (node (ref "R9") (pin "2") (pinfunction "2_2") (pintype "passive"))
      (node (ref "SOLENOID") (pin "2") (pinfunction "2_2") (pintype "passive"))
      (node (ref "SV1") (pin "1") (pinfunction "1_1") (pintype "passive"))
      (node (ref "SV1") (pin "11") (pinfunction "11_11") (pintype "passive"))
      (node (ref "SV1") (pin "13") (pinfunction "13_13") (pintype "passive"))
      (node (ref "SV1") (pin "15") (pinfunction "15_15") (pintype "passive"))
      (node (ref "SV1") (pin "17") (pinfunction "17_17") (pintype "passive"))
      (node (ref "SV1") (pin "19") (pinfunction "19_19") (pintype "passive"))
      (node (ref "SV1") (pin "21") (pinfunction "21_21") (pintype "passive"))
      (node (ref "SV1") (pin "23") (pinfunction "23_23") (pintype "passive"))
      (node (ref "SV1") (pin "25") (pinfunction "25_25") (pintype "passive"))
      (node (ref "SV1") (pin "27") (pinfunction "27_27") (pintype "passive"))
      (node (ref "SV1") (pin "3") (pinfunction "3_3") (pintype "passive"))
      (node (ref "SV1") (pin "5") (pinfunction "5_5") (pintype "passive"))
      (node (ref "SV1") (pin "7") (pinfunction "7_7") (pintype "passive"))
      (node (ref "SV1") (pin "9") (pinfunction "9_9") (pintype "passive"))
      (node (ref "TRIM") (pin "1") (pinfunction "1_1") (pintype "passive"))
      (node (ref "U$1") (pin "1") (pinfunction "A1_1") (pintype "bidirectional"))
      (node (ref "U$2") (pin "1") (pinfunction "A1_1") (pintype "bidirectional"))
      (node (ref "U$3") (pin "1") (pinfunction "A1_1") (pintype "bidirectional"))
      (node (ref "U1") (pin "21") (pinfunction "GND_21") (pintype "power_in"))
      (node (ref "U3") (pin "4") (pinfunction "-_2_4") (pintype "bidirectional"))
      (node (ref "Z1") (pin "A") (pinfunction "A_A") (pintype "passive"))
      (node (ref "Z2") (pin "A") (pinfunction "A_A") (pintype "passive"))
    )
    (net (code "26") (name "INT") (class "Default")
      (node (ref "OR_6") (pin "6") (pinfunction "Y2_6") (pintype "output"))
      (node (ref "Q1") (pin "3") (pinfunction "D_3") (pintype "passive"))
      (node (ref "R77") (pin "2") (pinfunction "2_2") (pintype "passive"))
    )
    (net (code "27") (name "INT_3V") (class "Default")
      (node (ref "Q1") (pin "2") (pinfunction "S_2") (pintype "passive"))
      (node (ref "R73") (pin "2") (pinfunction "2_2") (pintype "passive"))
      (node (ref "SV1") (pin "32") (pinfunction "32_32") (pintype "passive"))
    )
    (net (code "28") (name "IO0") (class "Default")
      (node (ref "IC1") (pin "20") (pinfunction "B1_20") (pintype "bidirectional"))
      (node (ref "OR_5") (pin "9") (pinfunction "A3_9") (pintype "input"))
      (node (ref "TP14") (pin "TP") (pinfunction "TP_TP") (pintype "input"))
      (node (ref "U1") (pin "18") (pinfunction "I/O0_18") (pintype "bidirectional"))
    )
    (net (code "29") (name "IO0,1") (class "Default")
      (node (ref "OR_5") (pin "8") (pinfunction "Y3_8") (pintype "output"))
      (node (ref "OR_6") (pin "10") (pinfunction "B3_10") (pintype "input"))
    )
    (net (code "30") (name "IO0,1,2,3") (class "Default")
      (node (ref "OR_6") (pin "5") (pinfunction "B2_5") (pintype "input"))
      (node (ref "OR_6") (pin "8") (pinfunction "Y3_8") (pintype "output"))
    )
    (net (code "31") (name "IO0_3V") (class "Default")
      (node (ref "IC1") (pin "1") (pinfunction "A1_1") (pintype "bidirectional"))
      (node (ref "SV1") (pin "40") (pinfunction "40_40") (pintype "passive"))
    )
    (net (code "32") (name "IO1") (class "Default")
      (node (ref "IC1") (pin "18") (pinfunction "B2_18") (pintype "bidirectional"))
      (node (ref "OR_5") (pin "10") (pinfunction "B3_10") (pintype "input"))
      (node (ref "TP17") (pin "TP") (pinfunction "TP_TP") (pintype "input"))
      (node (ref "U1") (pin "19") (pinfunction "I/O1_19") (pintype "bidirectional"))
    )
    (net (code "33") (name "IO1_3V") (class "Default")
      (node (ref "IC1") (pin "3") (pinfunction "A2_3") (pintype "bidirectional"))
      (node (ref "SV1") (pin "39") (pinfunction "39_39") (pintype "passive"))
    )
    (net (code "34") (name "IO2") (class "Default")
      (node (ref "IC1") (pin "17") (pinfunction "B3_17") (pintype "bidirectional"))
      (node (ref "OR_5") (pin "1") (pinfunction "A1_1") (pintype "input"))
      (node (ref "TP18") (pin "TP") (pinfunction "TP_TP") (pintype "input"))
      (node (ref "U1") (pin "20") (pinfunction "I/O2_20") (pintype "bidirectional"))
    )
    (net (code "35") (name "IO2,3") (class "Default")
      (node (ref "OR_5") (pin "3") (pinfunction "Y1_3") (pintype "output"))
      (node (ref "OR_6") (pin "9") (pinfunction "A3_9") (pintype "input"))
    )
    (net (code "36") (name "IO2_3V") (class "Default")
      (node (ref "IC1") (pin "4") (pinfunction "A3_4") (pintype "bidirectional"))
      (node (ref "SV1") (pin "38") (pinfunction "38_38") (pintype "passive"))
    )
    (net (code "37") (name "IO3") (class "Default")
      (node (ref "IC1") (pin "16") (pinfunction "B4_16") (pintype "bidirectional"))
      (node (ref "OR_5") (pin "2") (pinfunction "B1_2") (pintype "input"))
      (node (ref "TP19") (pin "TP") (pinfunction "TP_TP") (pintype "input"))
      (node (ref "U1") (pin "22") (pinfunction "I/O3_22") (pintype "bidirectional"))
    )
    (net (code "38") (name "IO3_3V") (class "Default")
      (node (ref "IC1") (pin "5") (pinfunction "A4_5") (pintype "bidirectional"))
      (node (ref "SV1") (pin "37") (pinfunction "37_37") (pintype "passive"))
    )
    (net (code "39") (name "IO4") (class "Default")
      (node (ref "IC1") (pin "15") (pinfunction "B5_15") (pintype "bidirectional"))
      (node (ref "OR_5") (pin "4") (pinfunction "A2_4") (pintype "input"))
      (node (ref "TP20") (pin "TP") (pinfunction "TP_TP") (pintype "input"))
      (node (ref "U1") (pin "23") (pinfunction "I/O4_23") (pintype "bidirectional"))
    )
    (net (code "40") (name "IO4,5") (class "Default")
      (node (ref "OR_5") (pin "6") (pinfunction "Y2_6") (pintype "output"))
      (node (ref "OR_6") (pin "1") (pinfunction "A1_1") (pintype "input"))
    )
    (net (code "41") (name "IO4,5,6,7") (class "Default")
      (node (ref "OR_6") (pin "3") (pinfunction "Y1_3") (pintype "output"))
      (node (ref "OR_6") (pin "4") (pinfunction "A2_4") (pintype "input"))
    )
    (net (code "42") (name "IO4_3V") (class "Default")
      (node (ref "IC1") (pin "6") (pinfunction "A5_6") (pintype "bidirectional"))
      (node (ref "SV1") (pin "36") (pinfunction "36_36") (pintype "passive"))
    )
    (net (code "43") (name "IO5") (class "Default")
      (node (ref "IC1") (pin "14") (pinfunction "B6_14") (pintype "bidirectional"))
      (node (ref "OR_5") (pin "5") (pinfunction "B2_5") (pintype "input"))
      (node (ref "TP21") (pin "TP") (pinfunction "TP_TP") (pintype "input"))
      (node (ref "U1") (pin "24") (pinfunction "I/O5_24") (pintype "bidirectional"))
    )
    (net (code "44") (name "IO5_3V") (class "Default")
      (node (ref "IC1") (pin "7") (pinfunction "A6_7") (pintype "bidirectional"))
      (node (ref "SV1") (pin "35") (pinfunction "35_35") (pintype "passive"))
    )
    (net (code "45") (name "IO6") (class "Default")
      (node (ref "IC1") (pin "13") (pinfunction "B7_13") (pintype "bidirectional"))
      (node (ref "OR_5") (pin "12") (pinfunction "A4_12") (pintype "input"))
      (node (ref "TP22") (pin "TP") (pinfunction "TP_TP") (pintype "input"))
      (node (ref "U1") (pin "25") (pinfunction "I/O6_25") (pintype "bidirectional"))
    )
    (net (code "46") (name "IO6,7") (class "Default")
      (node (ref "OR_5") (pin "11") (pinfunction "Y4_11") (pintype "output"))
      (node (ref "OR_6") (pin "2") (pinfunction "B1_2") (pintype "input"))
    )
    (net (code "47") (name "IO6_3V") (class "Default")
      (node (ref "IC1") (pin "8") (pinfunction "A7_8") (pintype "bidirectional"))
      (node (ref "SV1") (pin "34") (pinfunction "34_34") (pintype "passive"))
    )
    (net (code "48") (name "IO7") (class "Default")
      (node (ref "IC1") (pin "12") (pinfunction "B8_12") (pintype "bidirectional"))
      (node (ref "OR_5") (pin "13") (pinfunction "B4_13") (pintype "input"))
      (node (ref "TP23") (pin "TP") (pinfunction "TP_TP") (pintype "input"))
      (node (ref "U1") (pin "26") (pinfunction "I/O7_26") (pintype "bidirectional"))
    )
    (net (code "49") (name "IO7_3V") (class "Default")
      (node (ref "IC1") (pin "9") (pinfunction "A8_9") (pintype "bidirectional"))
      (node (ref "SV1") (pin "33") (pinfunction "33_33") (pintype "passive"))
    )
    (net (code "50") (name "KICK") (class "Default")
      (node (ref "Q2") (pin "G") (pinfunction "G_G") (pintype "passive"))
      (node (ref "R78") (pin "2") (pinfunction "2_2") (pintype "passive"))
      (node (ref "SV1") (pin "31") (pinfunction "31_31") (pintype "passive"))
    )
    (net (code "51") (name "L1") (class "Default")
      (node (ref "COMP_1") (pin "4") (pinfunction "4_4") (pintype "passive"))
      (node (ref "OR_1") (pin "1") (pinfunction "A1_1") (pintype "input"))
    )
    (net (code "52") (name "L2") (class "Default")
      (node (ref "COMP_2") (pin "4") (pinfunction "4_4") (pintype "passive"))
      (node (ref "OR_1") (pin "2") (pinfunction "B1_2") (pintype "input"))
    )
    (net (code "53") (name "L3") (class "Default")
      (node (ref "COMP_3") (pin "4") (pinfunction "4_4") (pintype "passive"))
      (node (ref "OR_1") (pin "4") (pinfunction "A2_4") (pintype "input"))
    )
    (net (code "54") (name "L4") (class "Default")
      (node (ref "COMP_4") (pin "4") (pinfunction "4_4") (pintype "passive"))
      (node (ref "OR_1") (pin "5") (pinfunction "B2_5") (pintype "input"))
    )
    (net (code "55") (name "L5") (class "Default")
      (node (ref "COMP_5") (pin "4") (pinfunction "4_4") (pintype "passive"))
      (node (ref "OR_1") (pin "9") (pinfunction "A3_9") (pintype "input"))
    )
    (net (code "56") (name "L6") (class "Default")
      (node (ref "COMP_6") (pin "4") (pinfunction "4_4") (pintype "passive"))
      (node (ref "OR_1") (pin "10") (pinfunction "B3_10") (pintype "input"))
    )
    (net (code "57") (name "L7") (class "Default")
      (node (ref "COMP_7") (pin "4") (pinfunction "4_4") (pintype "passive"))
      (node (ref "OR_1") (pin "12") (pinfunction "A4_12") (pintype "input"))
    )
    (net (code "58") (name "L8") (class "Default")
      (node (ref "COMP_8") (pin "4") (pinfunction "4_4") (pintype "passive"))
      (node (ref "OR_1") (pin "13") (pinfunction "B4_13") (pintype "input"))
    )
    (net (code "59") (name "L9") (class "Default")
      (node (ref "COMP_9") (pin "4") (pinfunction "4_4") (pintype "passive"))
      (node (ref "OR_2") (pin "1") (pinfunction "A1_1") (pintype "input"))
    )
    (net (code "60") (name "L10") (class "Default")
      (node (ref "COMP_10") (pin "4") (pinfunction "4_4") (pintype "passive"))
      (node (ref "OR_2") (pin "2") (pinfunction "B1_2") (pintype "input"))
    )
    (net (code "61") (name "L11") (class "Default")
      (node (ref "COMP_11") (pin "4") (pinfunction "4_4") (pintype "passive"))
      (node (ref "OR_2") (pin "4") (pinfunction "A2_4") (pintype "input"))
    )
    (net (code "62") (name "L12") (class "Default")
      (node (ref "COMP_12") (pin "4") (pinfunction "4_4") (pintype "passive"))
      (node (ref "OR_2") (pin "5") (pinfunction "B2_5") (pintype "input"))
    )
    (net (code "63") (name "L13") (class "Default")
      (node (ref "COMP_13") (pin "4") (pinfunction "4_4") (pintype "passive"))
      (node (ref "OR_2") (pin "9") (pinfunction "A3_9") (pintype "input"))
    )
    (net (code "64") (name "L14") (class "Default")
      (node (ref "COMP_14") (pin "4") (pinfunction "4_4") (pintype "passive"))
      (node (ref "OR_2") (pin "10") (pinfunction "B3_10") (pintype "input"))
    )
    (net (code "65") (name "L15") (class "Default")
      (node (ref "COMP_15") (pin "4") (pinfunction "4_4") (pintype "passive"))
      (node (ref "OR_2") (pin "12") (pinfunction "A4_12") (pintype "input"))
    )
    (net (code "66") (name "L16") (class "Default")
      (node (ref "COMP_16") (pin "4") (pinfunction "4_4") (pintype "passive"))
      (node (ref "OR_2") (pin "13") (pinfunction "B4_13") (pintype "input"))
    )
    (net (code "67") (name "L17") (class "Default")
      (node (ref "COMP_17") (pin "4") (pinfunction "4_4") (pintype "passive"))
      (node (ref "OR_3") (pin "1") (pinfunction "A1_1") (pintype "input"))
    )
    (net (code "68") (name "L18") (class "Default")
      (node (ref "COMP_18") (pin "4") (pinfunction "4_4") (pintype "passive"))
      (node (ref "OR_3") (pin "2") (pinfunction "B1_2") (pintype "input"))
    )
    (net (code "69") (name "L19") (class "Default")
      (node (ref "COMP_19") (pin "4") (pinfunction "4_4") (pintype "passive"))
      (node (ref "OR_3") (pin "4") (pinfunction "A2_4") (pintype "input"))
    )
    (net (code "70") (name "L20") (class "Default")
      (node (ref "COMP_20") (pin "4") (pinfunction "4_4") (pintype "passive"))
      (node (ref "OR_3") (pin "5") (pinfunction "B2_5") (pintype "input"))
    )
    (net (code "71") (name "L21") (class "Default")
      (node (ref "COMP_21") (pin "4") (pinfunction "4_4") (pintype "passive"))
      (node (ref "OR_3") (pin "9") (pinfunction "A3_9") (pintype "input"))
    )
    (net (code "72") (name "L22") (class "Default")
      (node (ref "COMP_22") (pin "4") (pinfunction "4_4") (pintype "passive"))
      (node (ref "OR_3") (pin "10") (pinfunction "B3_10") (pintype "input"))
    )
    (net (code "73") (name "L23") (class "Default")
      (node (ref "COMP_23") (pin "4") (pinfunction "4_4") (pintype "passive"))
      (node (ref "OR_3") (pin "12") (pinfunction "A4_12") (pintype "input"))
    )
    (net (code "74") (name "L24") (class "Default")
      (node (ref "COMP_24") (pin "4") (pinfunction "4_4") (pintype "passive"))
      (node (ref "OR_3") (pin "13") (pinfunction "B4_13") (pintype "input"))
    )
    (net (code "75") (name "L25") (class "Default")
      (node (ref "COMP_25") (pin "4") (pinfunction "4_4") (pintype "passive"))
      (node (ref "OR_4") (pin "1") (pinfunction "A1_1") (pintype "input"))
    )
    (net (code "76") (name "L26") (class "Default")
      (node (ref "COMP_26") (pin "4") (pinfunction "4_4") (pintype "passive"))
      (node (ref "OR_4") (pin "2") (pinfunction "B1_2") (pintype "input"))
    )
    (net (code "77") (name "L27") (class "Default")
      (node (ref "COMP_27") (pin "4") (pinfunction "4_4") (pintype "passive"))
      (node (ref "OR_4") (pin "4") (pinfunction "A2_4") (pintype "input"))
    )
    (net (code "78") (name "L28") (class "Default")
      (node (ref "COMP_28") (pin "4") (pinfunction "4_4") (pintype "passive"))
      (node (ref "OR_4") (pin "5") (pinfunction "B2_5") (pintype "input"))
    )
    (net (code "79") (name "L29") (class "Default")
      (node (ref "COMP_29") (pin "4") (pinfunction "4_4") (pintype "passive"))
      (node (ref "OR_4") (pin "9") (pinfunction "A3_9") (pintype "input"))
    )
    (net (code "80") (name "L30") (class "Default")
      (node (ref "COMP_30") (pin "4") (pinfunction "4_4") (pintype "passive"))
      (node (ref "OR_4") (pin "10") (pinfunction "B3_10") (pintype "input"))
    )
    (net (code "81") (name "Net-(C49-Pad+)") (class "Default")
      (node (ref "C49") (pin "+") (pinfunction "+_+") (pintype "passive"))
      (node (ref "C50") (pin "+") (pinfunction "+_+") (pintype "passive"))
      (node (ref "Q2") (pin "D") (pinfunction "D_D") (pintype "passive"))
      (node (ref "Q3") (pin "S") (pinfunction "S_S") (pintype "passive"))
      (node (ref "R80") (pin "1") (pinfunction "1_1") (pintype "passive"))
    )
    (net (code "82") (name "Net-(IO1-OUT)") (class "Default")
      (node (ref "IO1") (pin "2") (pinfunction "OUT_2") (pintype "output"))
      (node (ref "L1") (pin "1") (pinfunction "1_1") (pintype "passive"))
      (node (ref "Z2") (pin "C") (pinfunction "C_C") (pintype "passive"))
    )
    (net (code "83") (name "Net-(IO2-OUT)") (class "Default")
      (node (ref "IO2") (pin "2") (pinfunction "OUT_2") (pintype "output"))
      (node (ref "L2") (pin "1") (pinfunction "1_1") (pintype "passive"))
      (node (ref "Z1") (pin "C") (pinfunction "C_C") (pintype "passive"))
    )
    (net (code "84") (name "Net-(MAIN_POWER-2-COM)") (class "Default")
      (node (ref "FUSE") (pin "1") (pinfunction "1_1") (pintype "passive"))
      (node (ref "MAIN_POWER") (pin "2") (pinfunction "2-COM_2") (pintype "passive"))
    )
    (net (code "85") (name "Net-(Q2-PadS)") (class "Default")
      (node (ref "Q2") (pin "S") (pinfunction "S_S") (pintype "passive"))
      (node (ref "SOLENOID") (pin "1") (pinfunction "1_1") (pintype "passive"))
    )
    (net (code "86") (name "Net-(TCRT_1-CATHODE)") (class "Default")
      (node (ref "R1") (pin "1") (pinfunction "1_1") (pintype "passive"))
      (node (ref "TCRT_1") (pin "K") (pinfunction "CATHODE_K") (pintype "passive"))
    )
    (net (code "87") (name "Net-(TCRT_1-EMITTER)") (class "Default")
      (node (ref "COMP_1") (pin "3") (pinfunction "3_3") (pintype "passive"))
      (node (ref "R2") (pin "1") (pinfunction "1_1") (pintype "passive"))
      (node (ref "TCRT_1") (pin "E") (pinfunction "EMITTER_E") (pintype "passive"))
    )
    (net (code "88") (name "Net-(TCRT_2-CATHODE)") (class "Default")
      (node (ref "R3") (pin "1") (pinfunction "1_1") (pintype "passive"))
      (node (ref "TCRT_2") (pin "K") (pinfunction "CATHODE_K") (pintype "passive"))
    )
    (net (code "89") (name "Net-(TCRT_2-EMITTER)") (class "Default")
      (node (ref "COMP_2") (pin "3") (pinfunction "3_3") (pintype "passive"))
      (node (ref "R4") (pin "1") (pinfunction "1_1") (pintype "passive"))
      (node (ref "TCRT_2") (pin "E") (pinfunction "EMITTER_E") (pintype "passive"))
    )
    (net (code "90") (name "Net-(TCRT_3-CATHODE)") (class "Default")
      (node (ref "R5") (pin "1") (pinfunction "1_1") (pintype "passive"))
      (node (ref "TCRT_3") (pin "K") (pinfunction "CATHODE_K") (pintype "passive"))
    )
    (net (code "91") (name "Net-(TCRT_3-EMITTER)") (class "Default")
      (node (ref "COMP_3") (pin "3") (pinfunction "3_3") (pintype "passive"))
      (node (ref "R6") (pin "1") (pinfunction "1_1") (pintype "passive"))
      (node (ref "TCRT_3") (pin "E") (pinfunction "EMITTER_E") (pintype "passive"))
    )
    (net (code "92") (name "Net-(TCRT_4-CATHODE)") (class "Default")
      (node (ref "R7") (pin "1") (pinfunction "1_1") (pintype "passive"))
      (node (ref "TCRT_4") (pin "K") (pinfunction "CATHODE_K") (pintype "passive"))
    )
    (net (code "93") (name "Net-(TCRT_4-EMITTER)") (class "Default")
      (node (ref "COMP_4") (pin "3") (pinfunction "3_3") (pintype "passive"))
      (node (ref "R8") (pin "1") (pinfunction "1_1") (pintype "passive"))
      (node (ref "TCRT_4") (pin "E") (pinfunction "EMITTER_E") (pintype "passive"))
    )
    (net (code "94") (name "Net-(TCRT_5-CATHODE)") (class "Default")
      (node (ref "R9") (pin "1") (pinfunction "1_1") (pintype "passive"))
      (node (ref "TCRT_5") (pin "K") (pinfunction "CATHODE_K") (pintype "passive"))
    )
    (net (code "95") (name "Net-(TCRT_5-EMITTER)") (class "Default")
      (node (ref "COMP_5") (pin "3") (pinfunction "3_3") (pintype "passive"))
      (node (ref "R10") (pin "1") (pinfunction "1_1") (pintype "passive"))
      (node (ref "TCRT_5") (pin "E") (pinfunction "EMITTER_E") (pintype "passive"))
    )
    (net (code "96") (name "Net-(TCRT_6-CATHODE)") (class "Default")
      (node (ref "R11") (pin "1") (pinfunction "1_1") (pintype "passive"))
      (node (ref "TCRT_6") (pin "K") (pinfunction "CATHODE_K") (pintype "passive"))
    )
    (net (code "97") (name "Net-(TCRT_6-EMITTER)") (class "Default")
      (node (ref "COMP_6") (pin "3") (pinfunction "3_3") (pintype "passive"))
      (node (ref "R12") (pin "1") (pinfunction "1_1") (pintype "passive"))
      (node (ref "TCRT_6") (pin "E") (pinfunction "EMITTER_E") (pintype "passive"))
    )
    (net (code "98") (name "Net-(TCRT_7-CATHODE)") (class "Default")
      (node (ref "R13") (pin "1") (pinfunction "1_1") (pintype "passive"))
      (node (ref "TCRT_7") (pin "K") (pinfunction "CATHODE_K") (pintype "passive"))
    )
    (net (code "99") (name "Net-(TCRT_7-EMITTER)") (class "Default")
      (node (ref "COMP_7") (pin "3") (pinfunction "3_3") (pintype "passive"))
      (node (ref "R14") (pin "1") (pinfunction "1_1") (pintype "passive"))
      (node (ref "TCRT_7") (pin "E") (pinfunction "EMITTER_E") (pintype "passive"))
    )
    (net (code "100") (name "Net-(TCRT_8-CATHODE)") (class "Default")
      (node (ref "R15") (pin "1") (pinfunction "1_1") (pintype "passive"))
      (node (ref "TCRT_8") (pin "K") (pinfunction "CATHODE_K") (pintype "passive"))
    )
    (net (code "101") (name "Net-(TCRT_8-EMITTER)") (class "Default")
      (node (ref "COMP_8") (pin "3") (pinfunction "3_3") (pintype "passive"))
      (node (ref "R16") (pin "1") (pinfunction "1_1") (pintype "passive"))
      (node (ref "TCRT_8") (pin "E") (pinfunction "EMITTER_E") (pintype "passive"))
    )
    (net (code "102") (name "Net-(TCRT_9-CATHODE)") (class "Default")
      (node (ref "R17") (pin "1") (pinfunction "1_1") (pintype "passive"))
      (node (ref "TCRT_9") (pin "K") (pinfunction "CATHODE_K") (pintype "passive"))
    )
    (net (code "103") (name "Net-(TCRT_9-EMITTER)") (class "Default")
      (node (ref "COMP_9") (pin "3") (pinfunction "3_3") (pintype "passive"))
      (node (ref "R18") (pin "1") (pinfunction "1_1") (pintype "passive"))
      (node (ref "TCRT_9") (pin "E") (pinfunction "EMITTER_E") (pintype "passive"))
    )
    (net (code "104") (name "Net-(TCRT_10-CATHODE)") (class "Default")
      (node (ref "R19") (pin "1") (pinfunction "1_1") (pintype "passive"))
      (node (ref "TCRT_10") (pin "K") (pinfunction "CATHODE_K") (pintype "passive"))
    )
    (net (code "105") (name "Net-(TCRT_10-EMITTER)") (class "Default")
      (node (ref "COMP_10") (pin "3") (pinfunction "3_3") (pintype "passive"))
      (node (ref "R20") (pin "1") (pinfunction "1_1") (pintype "passive"))
      (node (ref "TCRT_10") (pin "E") (pinfunction "EMITTER_E") (pintype "passive"))
    )
    (net (code "106") (name "Net-(TCRT_11-CATHODE)") (class "Default")
      (node (ref "R21") (pin "1") (pinfunction "1_1") (pintype "passive"))
      (node (ref "TCRT_11") (pin "K") (pinfunction "CATHODE_K") (pintype "passive"))
    )
    (net (code "107") (name "Net-(TCRT_11-EMITTER)") (class "Default")
      (node (ref "COMP_11") (pin "3") (pinfunction "3_3") (pintype "passive"))
      (node (ref "R22") (pin "1") (pinfunction "1_1") (pintype "passive"))
      (node (ref "TCRT_11") (pin "E") (pinfunction "EMITTER_E") (pintype "passive"))
    )
    (net (code "108") (name "Net-(TCRT_12-CATHODE)") (class "Default")
      (node (ref "R23") (pin "1") (pinfunction "1_1") (pintype "passive"))
      (node (ref "TCRT_12") (pin "K") (pinfunction "CATHODE_K") (pintype "passive"))
    )
    (net (code "109") (name "Net-(TCRT_12-EMITTER)") (class "Default")
      (node (ref "COMP_12") (pin "3") (pinfunction "3_3") (pintype "passive"))
      (node (ref "R24") (pin "1") (pinfunction "1_1") (pintype "passive"))
      (node (ref "TCRT_12") (pin "E") (pinfunction "EMITTER_E") (pintype "passive"))
    )
    (net (code "110") (name "Net-(TCRT_13-CATHODE)") (class "Default")
      (node (ref "R25") (pin "1") (pinfunction "1_1") (pintype "passive"))
      (node (ref "TCRT_13") (pin "K") (pinfunction "CATHODE_K") (pintype "passive"))
    )
    (net (code "111") (name "Net-(TCRT_13-EMITTER)") (class "Default")
      (node (ref "COMP_13") (pin "3") (pinfunction "3_3") (pintype "passive"))
      (node (ref "R26") (pin "1") (pinfunction "1_1") (pintype "passive"))
      (node (ref "TCRT_13") (pin "E") (pinfunction "EMITTER_E") (pintype "passive"))
    )
    (net (code "112") (name "Net-(TCRT_14-CATHODE)") (class "Default")
      (node (ref "R27") (pin "1") (pinfunction "1_1") (pintype "passive"))
      (node (ref "TCRT_14") (pin "K") (pinfunction "CATHODE_K") (pintype "passive"))
    )
    (net (code "113") (name "Net-(TCRT_14-EMITTER)") (class "Default")
      (node (ref "COMP_14") (pin "3") (pinfunction "3_3") (pintype "passive"))
      (node (ref "R28") (pin "1") (pinfunction "1_1") (pintype "passive"))
      (node (ref "TCRT_14") (pin "E") (pinfunction "EMITTER_E") (pintype "passive"))
    )
    (net (code "114") (name "Net-(TCRT_15-CATHODE)") (class "Default")
      (node (ref "R29") (pin "1") (pinfunction "1_1") (pintype "passive"))
      (node (ref "TCRT_15") (pin "K") (pinfunction "CATHODE_K") (pintype "passive"))
    )
    (net (code "115") (name "Net-(TCRT_15-EMITTER)") (class "Default")
      (node (ref "COMP_15") (pin "3") (pinfunction "3_3") (pintype "passive"))
      (node (ref "R30") (pin "1") (pinfunction "1_1") (pintype "passive"))
      (node (ref "TCRT_15") (pin "E") (pinfunction "EMITTER_E") (pintype "passive"))
    )
    (net (code "116") (name "Net-(TCRT_16-CATHODE)") (class "Default")
      (node (ref "R31") (pin "1") (pinfunction "1_1") (pintype "passive"))
      (node (ref "TCRT_16") (pin "K") (pinfunction "CATHODE_K") (pintype "passive"))
    )
    (net (code "117") (name "Net-(TCRT_16-EMITTER)") (class "Default")
      (node (ref "COMP_16") (pin "3") (pinfunction "3_3") (pintype "passive"))
      (node (ref "R32") (pin "1") (pinfunction "1_1") (pintype "passive"))
      (node (ref "TCRT_16") (pin "E") (pinfunction "EMITTER_E") (pintype "passive"))
    )
    (net (code "118") (name "Net-(TCRT_17-CATHODE)") (class "Default")
      (node (ref "R33") (pin "1") (pinfunction "1_1") (pintype "passive"))
      (node (ref "TCRT_17") (pin "K") (pinfunction "CATHODE_K") (pintype "passive"))
    )
    (net (code "119") (name "Net-(TCRT_17-EMITTER)") (class "Default")
      (node (ref "COMP_17") (pin "3") (pinfunction "3_3") (pintype "passive"))
      (node (ref "R34") (pin "1") (pinfunction "1_1") (pintype "passive"))
      (node (ref "TCRT_17") (pin "E") (pinfunction "EMITTER_E") (pintype "passive"))
    )
    (net (code "120") (name "Net-(TCRT_18-CATHODE)") (class "Default")
      (node (ref "R35") (pin "1") (pinfunction "1_1") (pintype "passive"))
      (node (ref "TCRT_18") (pin "K") (pinfunction "CATHODE_K") (pintype "passive"))
    )
    (net (code "121") (name "Net-(TCRT_18-EMITTER)") (class "Default")
      (node (ref "COMP_18") (pin "3") (pinfunction "3_3") (pintype "passive"))
      (node (ref "R36") (pin "1") (pinfunction "1_1") (pintype "passive"))
      (node (ref "TCRT_18") (pin "E") (pinfunction "EMITTER_E") (pintype "passive"))
    )
    (net (code "122") (name "Net-(TCRT_19-CATHODE)") (class "Default")
      (node (ref "R37") (pin "1") (pinfunction "1_1") (pintype "passive"))
      (node (ref "TCRT_19") (pin "K") (pinfunction "CATHODE_K") (pintype "passive"))
    )
    (net (code "123") (name "Net-(TCRT_19-EMITTER)") (class "Default")
      (node (ref "COMP_19") (pin "3") (pinfunction "3_3") (pintype "passive"))
      (node (ref "R38") (pin "1") (pinfunction "1_1") (pintype "passive"))
      (node (ref "TCRT_19") (pin "E") (pinfunction "EMITTER_E") (pintype "passive"))
    )
    (net (code "124") (name "Net-(TCRT_20-CATHODE)") (class "Default")
      (node (ref "R39") (pin "1") (pinfunction "1_1") (pintype "passive"))
      (node (ref "TCRT_20") (pin "K") (pinfunction "CATHODE_K") (pintype "passive"))
    )
    (net (code "125") (name "Net-(TCRT_20-EMITTER)") (class "Default")
      (node (ref "COMP_20") (pin "3") (pinfunction "3_3") (pintype "passive"))
      (node (ref "R40") (pin "1") (pinfunction "1_1") (pintype "passive"))
      (node (ref "TCRT_20") (pin "E") (pinfunction "EMITTER_E") (pintype "passive"))
    )
    (net (code "126") (name "Net-(TCRT_21-CATHODE)") (class "Default")
      (node (ref "R41") (pin "1") (pinfunction "1_1") (pintype "passive"))
      (node (ref "TCRT_21") (pin "K") (pinfunction "CATHODE_K") (pintype "passive"))
    )
    (net (code "127") (name "Net-(TCRT_21-EMITTER)") (class "Default")
      (node (ref "COMP_21") (pin "3") (pinfunction "3_3") (pintype "passive"))
      (node (ref "R42") (pin "1") (pinfunction "1_1") (pintype "passive"))
      (node (ref "TCRT_21") (pin "E") (pinfunction "EMITTER_E") (pintype "passive"))
    )
    (net (code "128") (name "Net-(TCRT_22-CATHODE)") (class "Default")
      (node (ref "R43") (pin "1") (pinfunction "1_1") (pintype "passive"))
      (node (ref "TCRT_22") (pin "K") (pinfunction "CATHODE_K") (pintype "passive"))
    )
    (net (code "129") (name "Net-(TCRT_22-EMITTER)") (class "Default")
      (node (ref "COMP_22") (pin "3") (pinfunction "3_3") (pintype "passive"))
      (node (ref "R44") (pin "1") (pinfunction "1_1") (pintype "passive"))
      (node (ref "TCRT_22") (pin "E") (pinfunction "EMITTER_E") (pintype "passive"))
    )
    (net (code "130") (name "Net-(TCRT_23-CATHODE)") (class "Default")
      (node (ref "R45") (pin "1") (pinfunction "1_1") (pintype "passive"))
      (node (ref "TCRT_23") (pin "K") (pinfunction "CATHODE_K") (pintype "passive"))
    )
    (net (code "131") (name "Net-(TCRT_23-EMITTER)") (class "Default")
      (node (ref "COMP_23") (pin "3") (pinfunction "3_3") (pintype "passive"))
      (node (ref "R46") (pin "1") (pinfunction "1_1") (pintype "passive"))
      (node (ref "TCRT_23") (pin "E") (pinfunction "EMITTER_E") (pintype "passive"))
    )
    (net (code "132") (name "Net-(TCRT_24-CATHODE)") (class "Default")
      (node (ref "R47") (pin "1") (pinfunction "1_1") (pintype "passive"))
      (node (ref "TCRT_24") (pin "K") (pinfunction "CATHODE_K") (pintype "passive"))
    )
    (net (code "133") (name "Net-(TCRT_24-EMITTER)") (class "Default")
      (node (ref "COMP_24") (pin "3") (pinfunction "3_3") (pintype "passive"))
      (node (ref "R48") (pin "1") (pinfunction "1_1") (pintype "passive"))
      (node (ref "TCRT_24") (pin "E") (pinfunction "EMITTER_E") (pintype "passive"))
    )
    (net (code "134") (name "Net-(TCRT_25-CATHODE)") (class "Default")
      (node (ref "R49") (pin "1") (pinfunction "1_1") (pintype "passive"))
      (node (ref "TCRT_25") (pin "K") (pinfunction "CATHODE_K") (pintype "passive"))
    )
    (net (code "135") (name "Net-(TCRT_25-EMITTER)") (class "Default")
      (node (ref "COMP_25") (pin "3") (pinfunction "3_3") (pintype "passive"))
      (node (ref "R50") (pin "1") (pinfunction "1_1") (pintype "passive"))
      (node (ref "TCRT_25") (pin "E") (pinfunction "EMITTER_E") (pintype "passive"))
    )
    (net (code "136") (name "Net-(TCRT_26-CATHODE)") (class "Default")
      (node (ref "R51") (pin "1") (pinfunction "1_1") (pintype "passive"))
      (node (ref "TCRT_26") (pin "K") (pinfunction "CATHODE_K") (pintype "passive"))
    )
    (net (code "137") (name "Net-(TCRT_26-EMITTER)") (class "Default")
      (node (ref "COMP_26") (pin "3") (pinfunction "3_3") (pintype "passive"))
      (node (ref "R52") (pin "1") (pinfunction "1_1") (pintype "passive"))
      (node (ref "TCRT_26") (pin "E") (pinfunction "EMITTER_E") (pintype "passive"))
    )
    (net (code "138") (name "Net-(TCRT_27-CATHODE)") (class "Default")
      (node (ref "R53") (pin "1") (pinfunction "1_1") (pintype "passive"))
      (node (ref "TCRT_27") (pin "K") (pinfunction "CATHODE_K") (pintype "passive"))
    )
    (net (code "139") (name "Net-(TCRT_27-EMITTER)") (class "Default")
      (node (ref "COMP_27") (pin "3") (pinfunction "3_3") (pintype "passive"))
      (node (ref "R54") (pin "1") (pinfunction "1_1") (pintype "passive"))
      (node (ref "TCRT_27") (pin "E") (pinfunction "EMITTER_E") (pintype "passive"))
    )
    (net (code "140") (name "Net-(TCRT_28-CATHODE)") (class "Default")
      (node (ref "R55") (pin "1") (pinfunction "1_1") (pintype "passive"))
      (node (ref "TCRT_28") (pin "K") (pinfunction "CATHODE_K") (pintype "passive"))
    )
    (net (code "141") (name "Net-(TCRT_28-EMITTER)") (class "Default")
      (node (ref "COMP_28") (pin "3") (pinfunction "3_3") (pintype "passive"))
      (node (ref "R56") (pin "1") (pinfunction "1_1") (pintype "passive"))
      (node (ref "TCRT_28") (pin "E") (pinfunction "EMITTER_E") (pintype "passive"))
    )
    (net (code "142") (name "Net-(TCRT_29-CATHODE)") (class "Default")
      (node (ref "R57") (pin "1") (pinfunction "1_1") (pintype "passive"))
      (node (ref "TCRT_29") (pin "K") (pinfunction "CATHODE_K") (pintype "passive"))
    )
    (net (code "143") (name "Net-(TCRT_29-EMITTER)") (class "Default")
      (node (ref "COMP_29") (pin "3") (pinfunction "3_3") (pintype "passive"))
      (node (ref "R58") (pin "1") (pinfunction "1_1") (pintype "passive"))
      (node (ref "TCRT_29") (pin "E") (pinfunction "EMITTER_E") (pintype "passive"))
    )
    (net (code "144") (name "Net-(TCRT_30-CATHODE)") (class "Default")
      (node (ref "R59") (pin "1") (pinfunction "1_1") (pintype "passive"))
      (node (ref "TCRT_30") (pin "K") (pinfunction "CATHODE_K") (pintype "passive"))
    )
    (net (code "145") (name "Net-(TCRT_30-EMITTER)") (class "Default")
      (node (ref "COMP_30") (pin "3") (pinfunction "3_3") (pintype "passive"))
      (node (ref "R60") (pin "1") (pinfunction "1_1") (pintype "passive"))
      (node (ref "TCRT_30") (pin "E") (pinfunction "EMITTER_E") (pintype "passive"))
    )
    (net (code "146") (name "Net-(U2-+_1)") (class "Default")
      (node (ref "FUSE") (pin "2") (pinfunction "2_2") (pintype "passive"))
      (node (ref "FUSE1") (pin "2") (pinfunction "2_2") (pintype "passive"))
      (node (ref "FUSE2") (pin "2") (pinfunction "2_2") (pintype "passive"))
      (node (ref "U2") (pin "1") (pinfunction "+_1_1") (pintype "bidirectional"))
    )
    (net (code "147") (name "Net-(U2-+_2)") (class "Default")
      (node (ref "U2") (pin "3") (pinfunction "+_2_3") (pintype "bidirectional"))
      (node (ref "U2") (pin "4") (pinfunction "-_2_4") (pintype "bidirectional"))
    )
    (net (code "148") (name "Net-(U2--_1)") (class "Default")
      (node (ref "U2") (pin "2") (pinfunction "-_1_2") (pintype "bidirectional"))
      (node (ref "U3") (pin "3") (pinfunction "+_2_3") (pintype "bidirectional"))
    )
    (net (code "149") (name "Net-(U3-+_1)") (class "Default")
      (node (ref "U3") (pin "1") (pinfunction "+_1_1") (pintype "bidirectional"))
      (node (ref "U3") (pin "2") (pinfunction "-_1_2") (pintype "bidirectional"))
    )
    (net (code "150") (name "REF") (class "Default")
      (node (ref "C52") (pin "2") (pinfunction "2_2") (pintype "passive"))
      (node (ref "COMP_1") (pin "1") (pinfunction "1_1") (pintype "passive"))
      (node (ref "COMP_10") (pin "1") (pinfunction "1_1") (pintype "passive"))
      (node (ref "COMP_11") (pin "1") (pinfunction "1_1") (pintype "passive"))
      (node (ref "COMP_12") (pin "1") (pinfunction "1_1") (pintype "passive"))
      (node (ref "COMP_13") (pin "1") (pinfunction "1_1") (pintype "passive"))
      (node (ref "COMP_14") (pin "1") (pinfunction "1_1") (pintype "passive"))
      (node (ref "COMP_15") (pin "1") (pinfunction "1_1") (pintype "passive"))
      (node (ref "COMP_16") (pin "1") (pinfunction "1_1") (pintype "passive"))
      (node (ref "COMP_17") (pin "1") (pinfunction "1_1") (pintype "passive"))
      (node (ref "COMP_18") (pin "1") (pinfunction "1_1") (pintype "passive"))
      (node (ref "COMP_19") (pin "1") (pinfunction "1_1") (pintype "passive"))
      (node (ref "COMP_2") (pin "1") (pinfunction "1_1") (pintype "passive"))
      (node (ref "COMP_20") (pin "1") (pinfunction "1_1") (pintype "passive"))
      (node (ref "COMP_21") (pin "1") (pinfunction "1_1") (pintype "passive"))
      (node (ref "COMP_22") (pin "1") (pinfunction "1_1") (pintype "passive"))
      (node (ref "COMP_23") (pin "1") (pinfunction "1_1") (pintype "passive"))
      (node (ref "COMP_24") (pin "1") (pinfunction "1_1") (pintype "passive"))
      (node (ref "COMP_25") (pin "1") (pinfunction "1_1") (pintype "passive"))
      (node (ref "COMP_26") (pin "1") (pinfunction "1_1") (pintype "passive"))
      (node (ref "COMP_27") (pin "1") (pinfunction "1_1") (pintype "passive"))
      (node (ref "COMP_28") (pin "1") (pinfunction "1_1") (pintype "passive"))
      (node (ref "COMP_29") (pin "1") (pinfunction "1_1") (pintype "passive"))
      (node (ref "COMP_3") (pin "1") (pinfunction "1_1") (pintype "passive"))
      (node (ref "COMP_30") (pin "1") (pinfunction "1_1") (pintype "passive"))
      (node (ref "COMP_4") (pin "1") (pinfunction "1_1") (pintype "passive"))
      (node (ref "COMP_5") (pin "1") (pinfunction "1_1") (pintype "passive"))
      (node (ref "COMP_6") (pin "1") (pinfunction "1_1") (pintype "passive"))
      (node (ref "COMP_7") (pin "1") (pinfunction "1_1") (pintype "passive"))
      (node (ref "COMP_8") (pin "1") (pinfunction "1_1") (pintype "passive"))
      (node (ref "COMP_9") (pin "1") (pinfunction "1_1") (pintype "passive"))
      (node (ref "TRIM") (pin "2") (pinfunction "2_2") (pintype "passive"))
    )
    (net (code "151") (name "SOLENOID") (class "Default")
      (node (ref "FUSE2") (pin "1") (pinfunction "1_1") (pintype "passive"))
      (node (ref "Q3") (pin "D") (pinfunction "D_D") (pintype "passive"))
    )
    (net (code "152") (name "V_CAP") (class "Default")
      (node (ref "R80") (pin "2") (pinfunction "2_2") (pintype "passive"))
      (node (ref "R81") (pin "1") (pinfunction "1_1") (pintype "passive"))
      (node (ref "SV1") (pin "29") (pinfunction "29_29") (pintype "passive"))
    )
    (net (code "153") (name "Y1") (class "Default")
      (node (ref "OR_1") (pin "3") (pinfunction "Y1_3") (pintype "output"))
      (node (ref "R63") (pin "2") (pinfunction "2_2") (pintype "passive"))
    )
    (net (code "154") (name "Y2") (class "Default")
      (node (ref "OR_1") (pin "6") (pinfunction "Y2_6") (pintype "output"))
      (node (ref "R64") (pin "2") (pinfunction "2_2") (pintype "passive"))
    )
    (net (code "155") (name "Y3") (class "Default")
      (node (ref "OR_1") (pin "8") (pinfunction "Y3_8") (pintype "output"))
      (node (ref "R62") (pin "2") (pinfunction "2_2") (pintype "passive"))
    )
    (net (code "156") (name "Y4") (class "Default")
      (node (ref "OR_1") (pin "11") (pinfunction "Y4_11") (pintype "output"))
      (node (ref "R61") (pin "2") (pinfunction "2_2") (pintype "passive"))
    )
    (net (code "157") (name "Y5") (class "Default")
      (node (ref "OR_2") (pin "3") (pinfunction "Y1_3") (pintype "output"))
      (node (ref "R68") (pin "2") (pinfunction "2_2") (pintype "passive"))
    )
    (net (code "158") (name "Y6") (class "Default")
      (node (ref "OR_2") (pin "6") (pinfunction "Y2_6") (pintype "output"))
      (node (ref "R67") (pin "2") (pinfunction "2_2") (pintype "passive"))
    )
    (net (code "159") (name "Y7") (class "Default")
      (node (ref "OR_2") (pin "8") (pinfunction "Y3_8") (pintype "output"))
      (node (ref "R66") (pin "2") (pinfunction "2_2") (pintype "passive"))
    )
    (net (code "160") (name "Y8") (class "Default")
      (node (ref "OR_2") (pin "11") (pinfunction "Y4_11") (pintype "output"))
      (node (ref "R65") (pin "2") (pinfunction "2_2") (pintype "passive"))
    )
    (net (code "161") (name "Y9") (class "Default")
      (node (ref "OR_3") (pin "3") (pinfunction "Y1_3") (pintype "output"))
      (node (ref "R72") (pin "2") (pinfunction "2_2") (pintype "passive"))
    )
    (net (code "162") (name "Y10") (class "Default")
      (node (ref "OR_3") (pin "6") (pinfunction "Y2_6") (pintype "output"))
      (node (ref "R71") (pin "2") (pinfunction "2_2") (pintype "passive"))
    )
    (net (code "163") (name "Y11") (class "Default")
      (node (ref "OR_3") (pin "8") (pinfunction "Y3_8") (pintype "output"))
      (node (ref "R70") (pin "2") (pinfunction "2_2") (pintype "passive"))
    )
    (net (code "164") (name "Y12") (class "Default")
      (node (ref "OR_3") (pin "11") (pinfunction "Y4_11") (pintype "output"))
      (node (ref "R69") (pin "2") (pinfunction "2_2") (pintype "passive"))
    )
    (net (code "165") (name "Y13") (class "Default")
      (node (ref "OR_4") (pin "3") (pinfunction "Y1_3") (pintype "output"))
      (node (ref "R76") (pin "2") (pinfunction "2_2") (pintype "passive"))
    )
    (net (code "166") (name "Y14") (class "Default")
      (node (ref "OR_4") (pin "6") (pinfunction "Y2_6") (pintype "output"))
      (node (ref "R75") (pin "2") (pinfunction "2_2") (pintype "passive"))
    )
    (net (code "167") (name "Y15") (class "Default")
      (node (ref "OR_4") (pin "8") (pinfunction "Y3_8") (pintype "output"))
      (node (ref "R74") (pin "2") (pinfunction "2_2") (pintype "passive"))
    )
    (net (code "168") (name "unconnected-(MAIN_POWER-1-OFF-Pad1)") (class "Default")
      (node (ref "MAIN_POWER") (pin "1") (pinfunction "1-OFF_1") (pintype "passive"))
    )
    (net (code "169") (name "unconnected-(OR_4-A4-Pad12)") (class "Default")
      (node (ref "OR_4") (pin "12") (pinfunction "A4_12") (pintype "input"))
    )
    (net (code "170") (name "unconnected-(OR_4-B4-Pad13)") (class "Default")
      (node (ref "OR_4") (pin "13") (pinfunction "B4_13") (pintype "input"))
    )
    (net (code "171") (name "unconnected-(OR_4-Y4-Pad11)") (class "Default")
      (node (ref "OR_4") (pin "11") (pinfunction "Y4_11") (pintype "output"))
    )
    (net (code "172") (name "unconnected-(OR_6-A4-Pad12)") (class "Default")
      (node (ref "OR_6") (pin "12") (pinfunction "A4_12") (pintype "input"))
    )
    (net (code "173") (name "unconnected-(OR_6-B4-Pad13)") (class "Default")
      (node (ref "OR_6") (pin "13") (pinfunction "B4_13") (pintype "input"))
    )
    (net (code "174") (name "unconnected-(OR_6-Y4-Pad11)") (class "Default")
      (node (ref "OR_6") (pin "11") (pinfunction "Y4_11") (pintype "output"))
    )
    (net (code "175") (name "unconnected-(U2-Pad5)") (class "Default")
      (node (ref "U2") (pin "5") (pinfunction "5_5") (pintype "bidirectional"))
    )
    (net (code "176") (name "unconnected-(U2-Pad6)") (class "Default")
      (node (ref "U2") (pin "6") (pinfunction "6_6") (pintype "bidirectional"))
    )
    (net (code "177") (name "unconnected-(U3-Pad5)") (class "Default")
      (node (ref "U3") (pin "5") (pinfunction "5_5") (pintype "bidirectional"))
    )
    (net (code "178") (name "unconnected-(U3-Pad6)") (class "Default")
      (node (ref "U3") (pin "6") (pinfunction "6_6") (pintype "bidirectional"))
    )
    (net (code "179") (name "unconnected-(X1-Pad1)") (class "Default")
      (node (ref "X1") (pin "1") (pinfunction "1_1") (pintype "passive"))
    )
    (net (code "180") (name "unconnected-(X1-Pad2)") (class "Default")
      (node (ref "X1") (pin "2") (pinfunction "2_2") (pintype "passive"))
    )
    (net (code "181") (name "unconnected-(X2-Pad1)") (class "Default")
      (node (ref "X2") (pin "1") (pinfunction "1_1") (pintype "passive"))
    )
    (net (code "182") (name "unconnected-(X2-Pad2)") (class "Default")
      (node (ref "X2") (pin "2") (pinfunction "2_2") (pintype "passive"))
    )
  )
)
